# MicroMouse_v03_full_plane.net
KiCad netlist of a schematic drawn in EasyEDA Pro
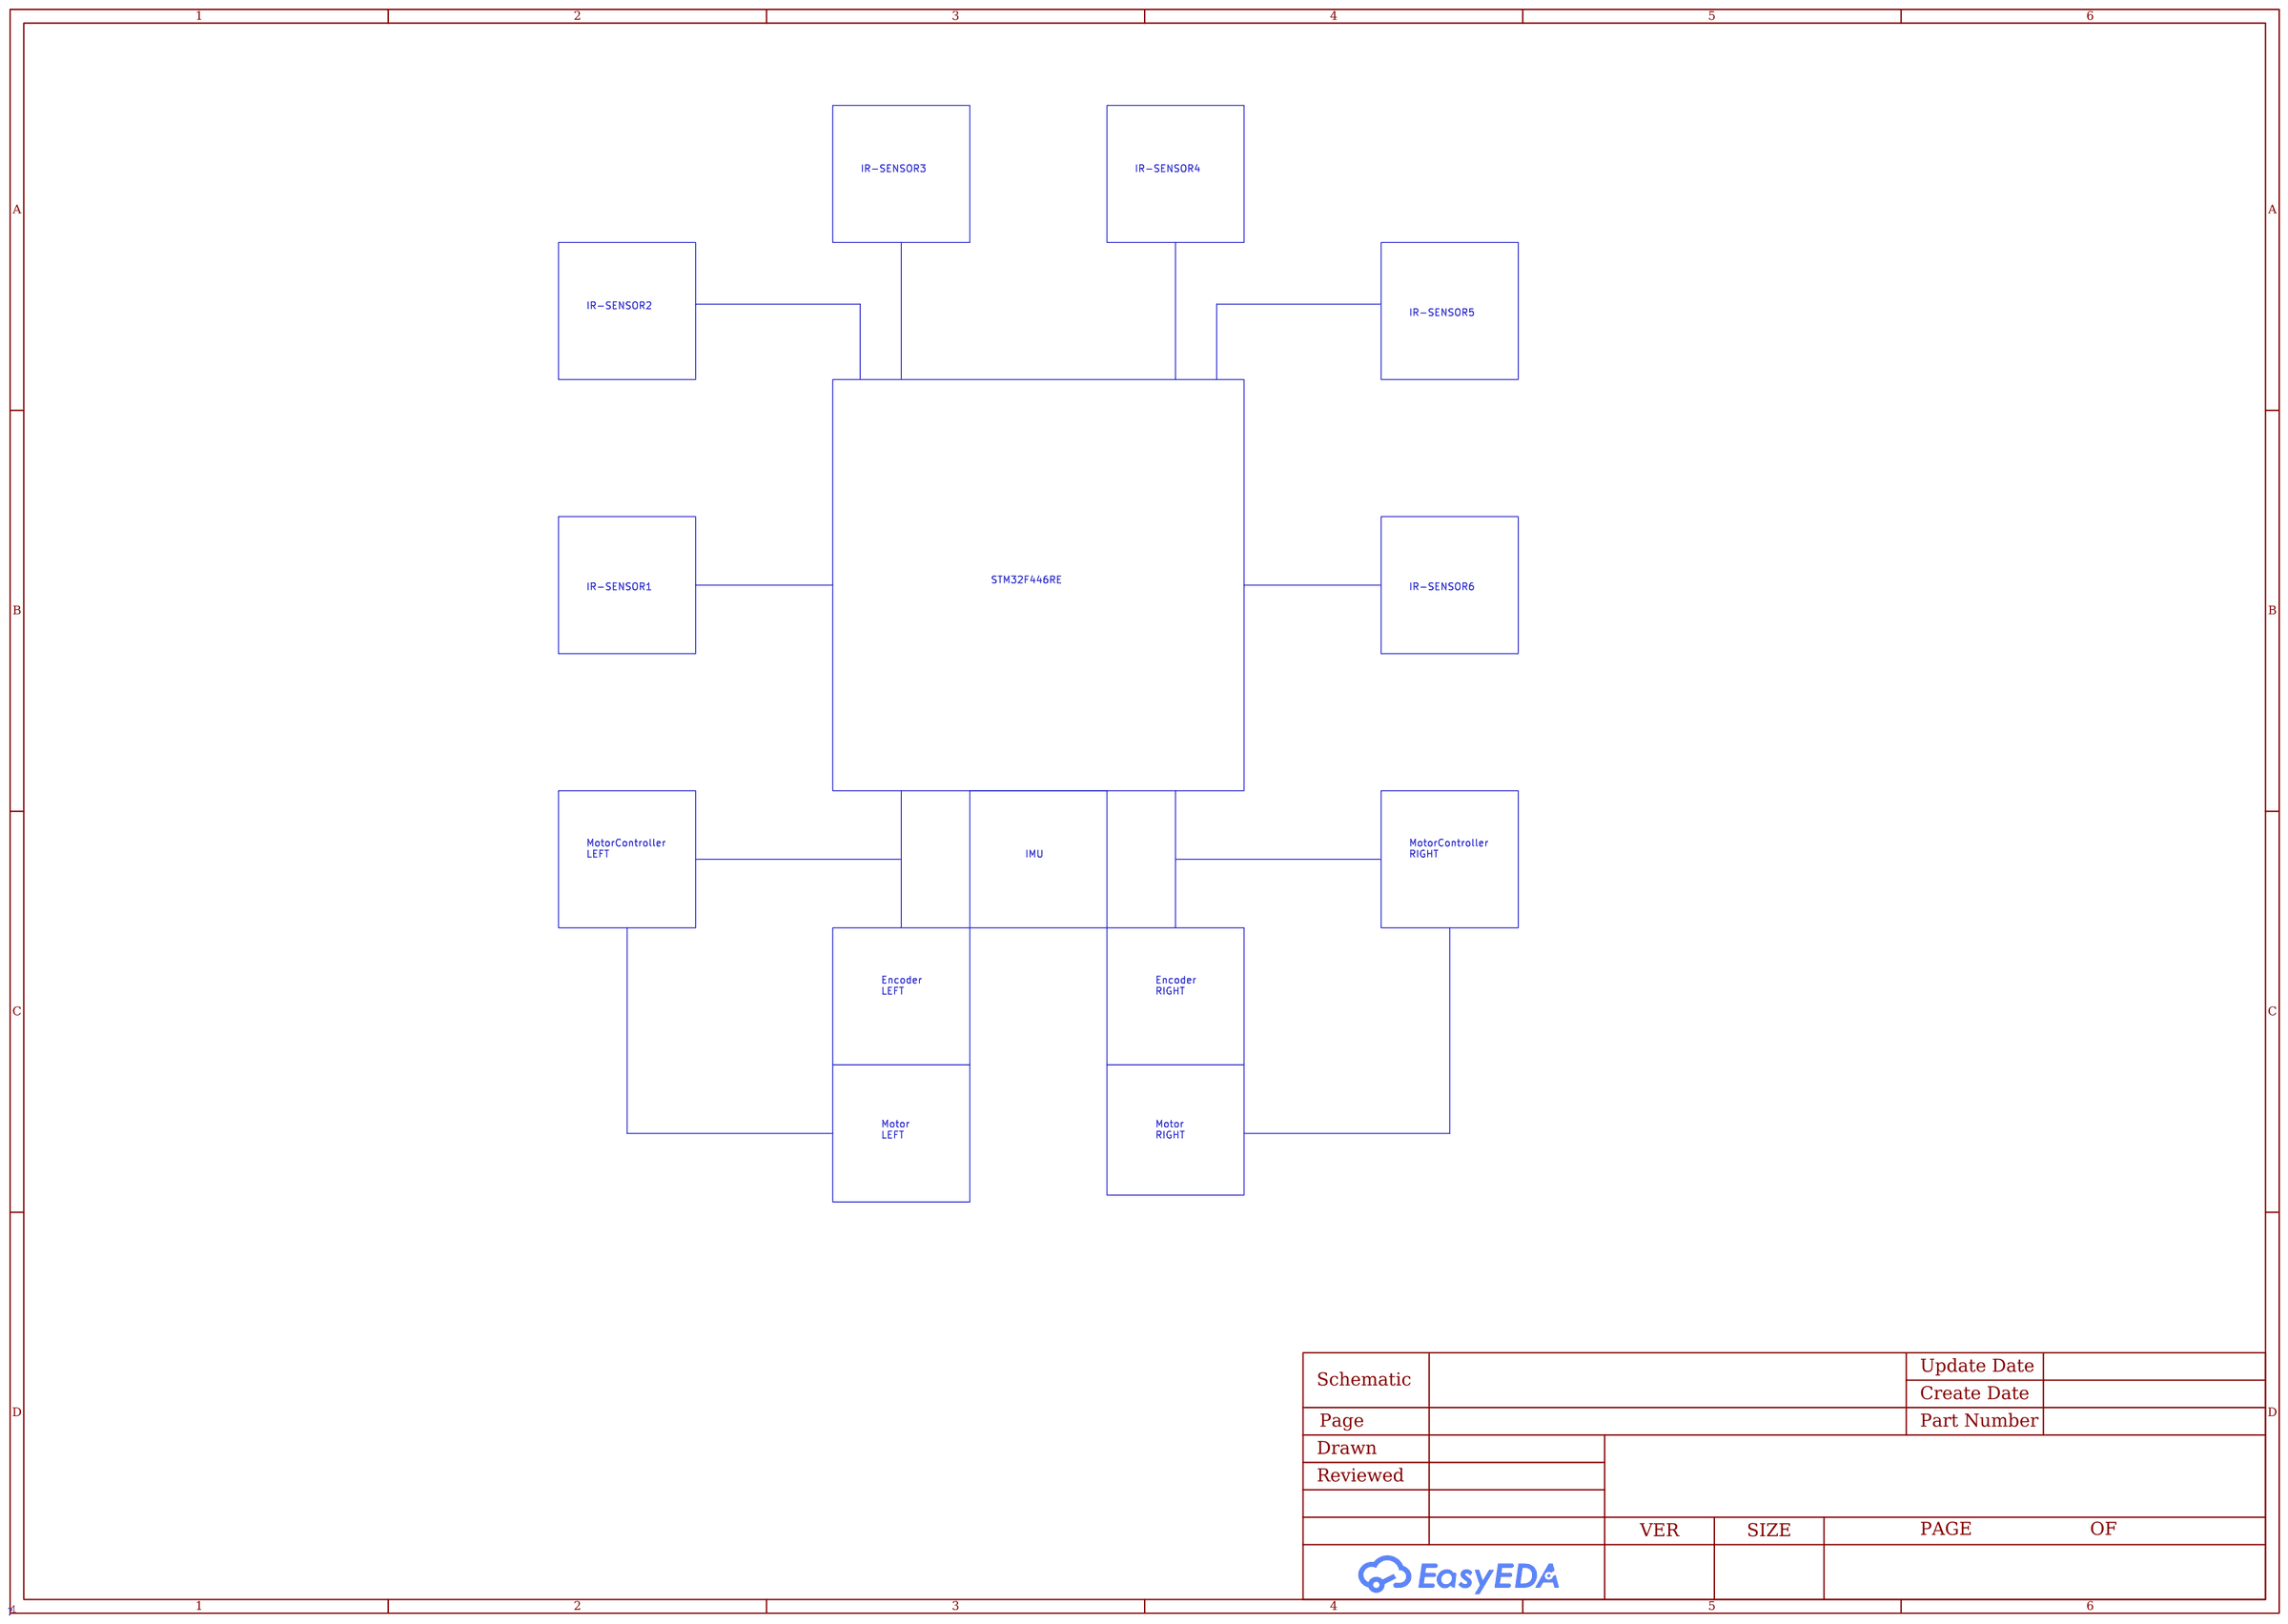
[diagram p0: Overview]
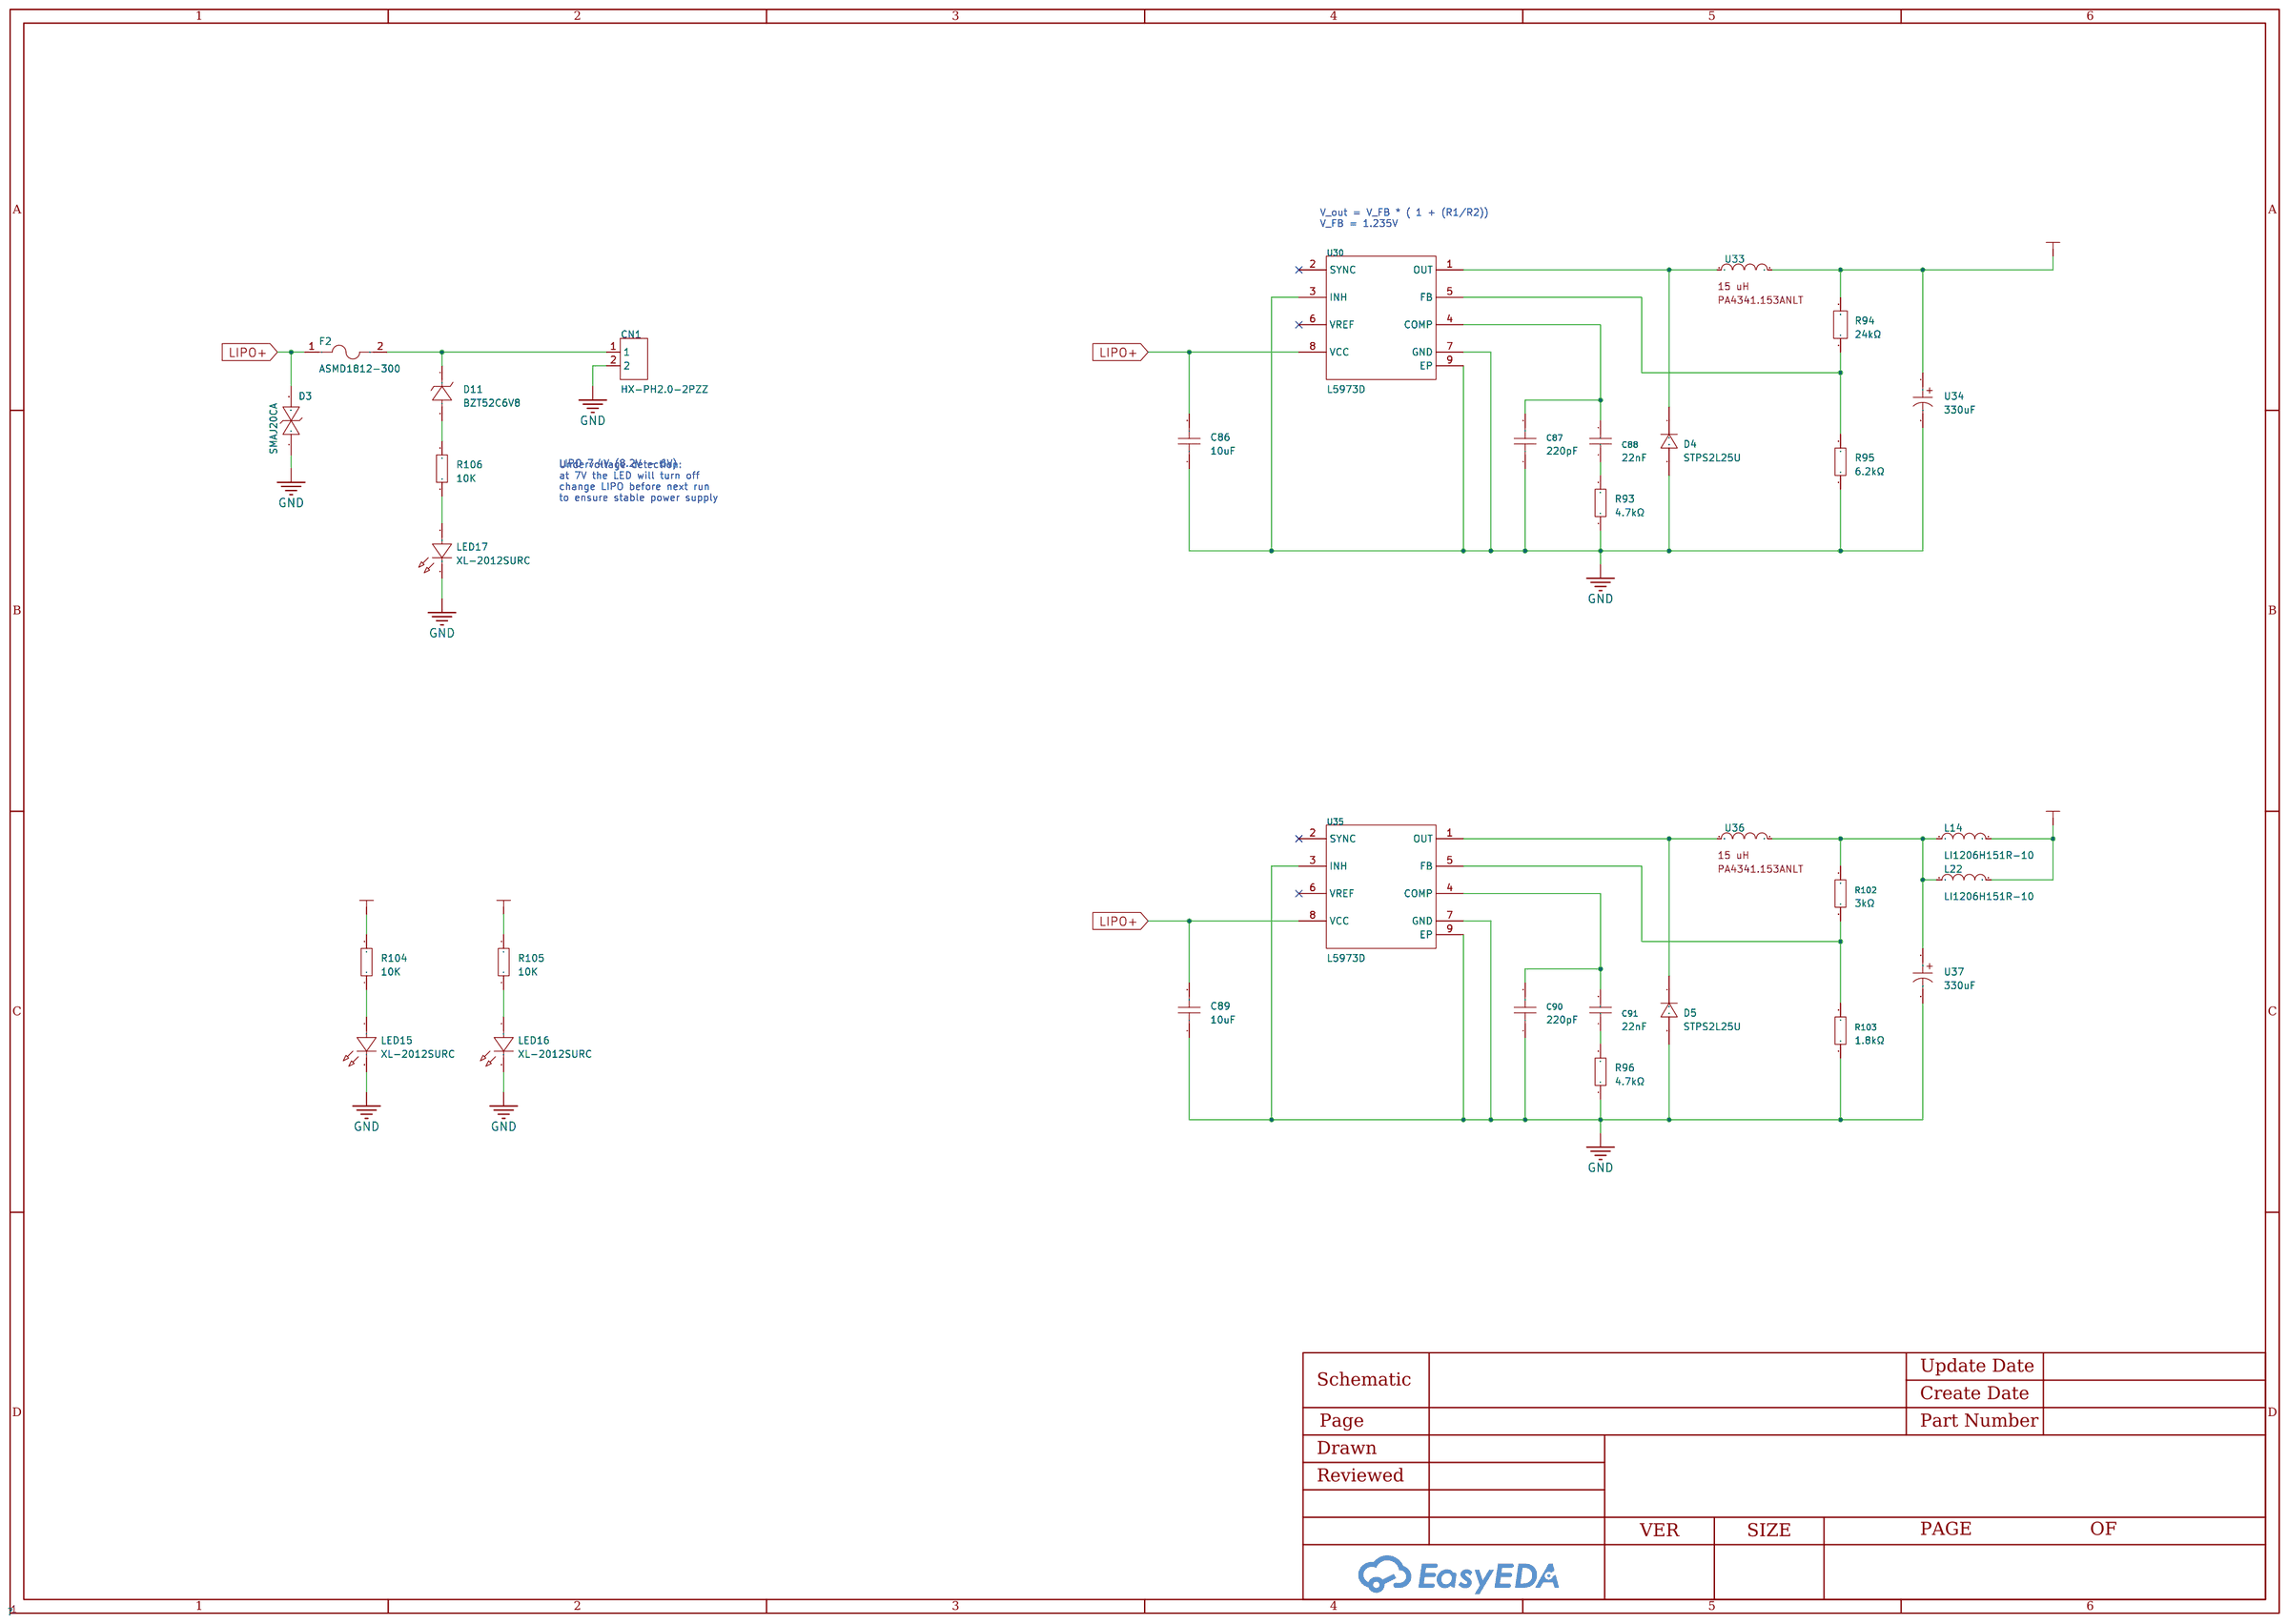
[diagram p1: VCC]
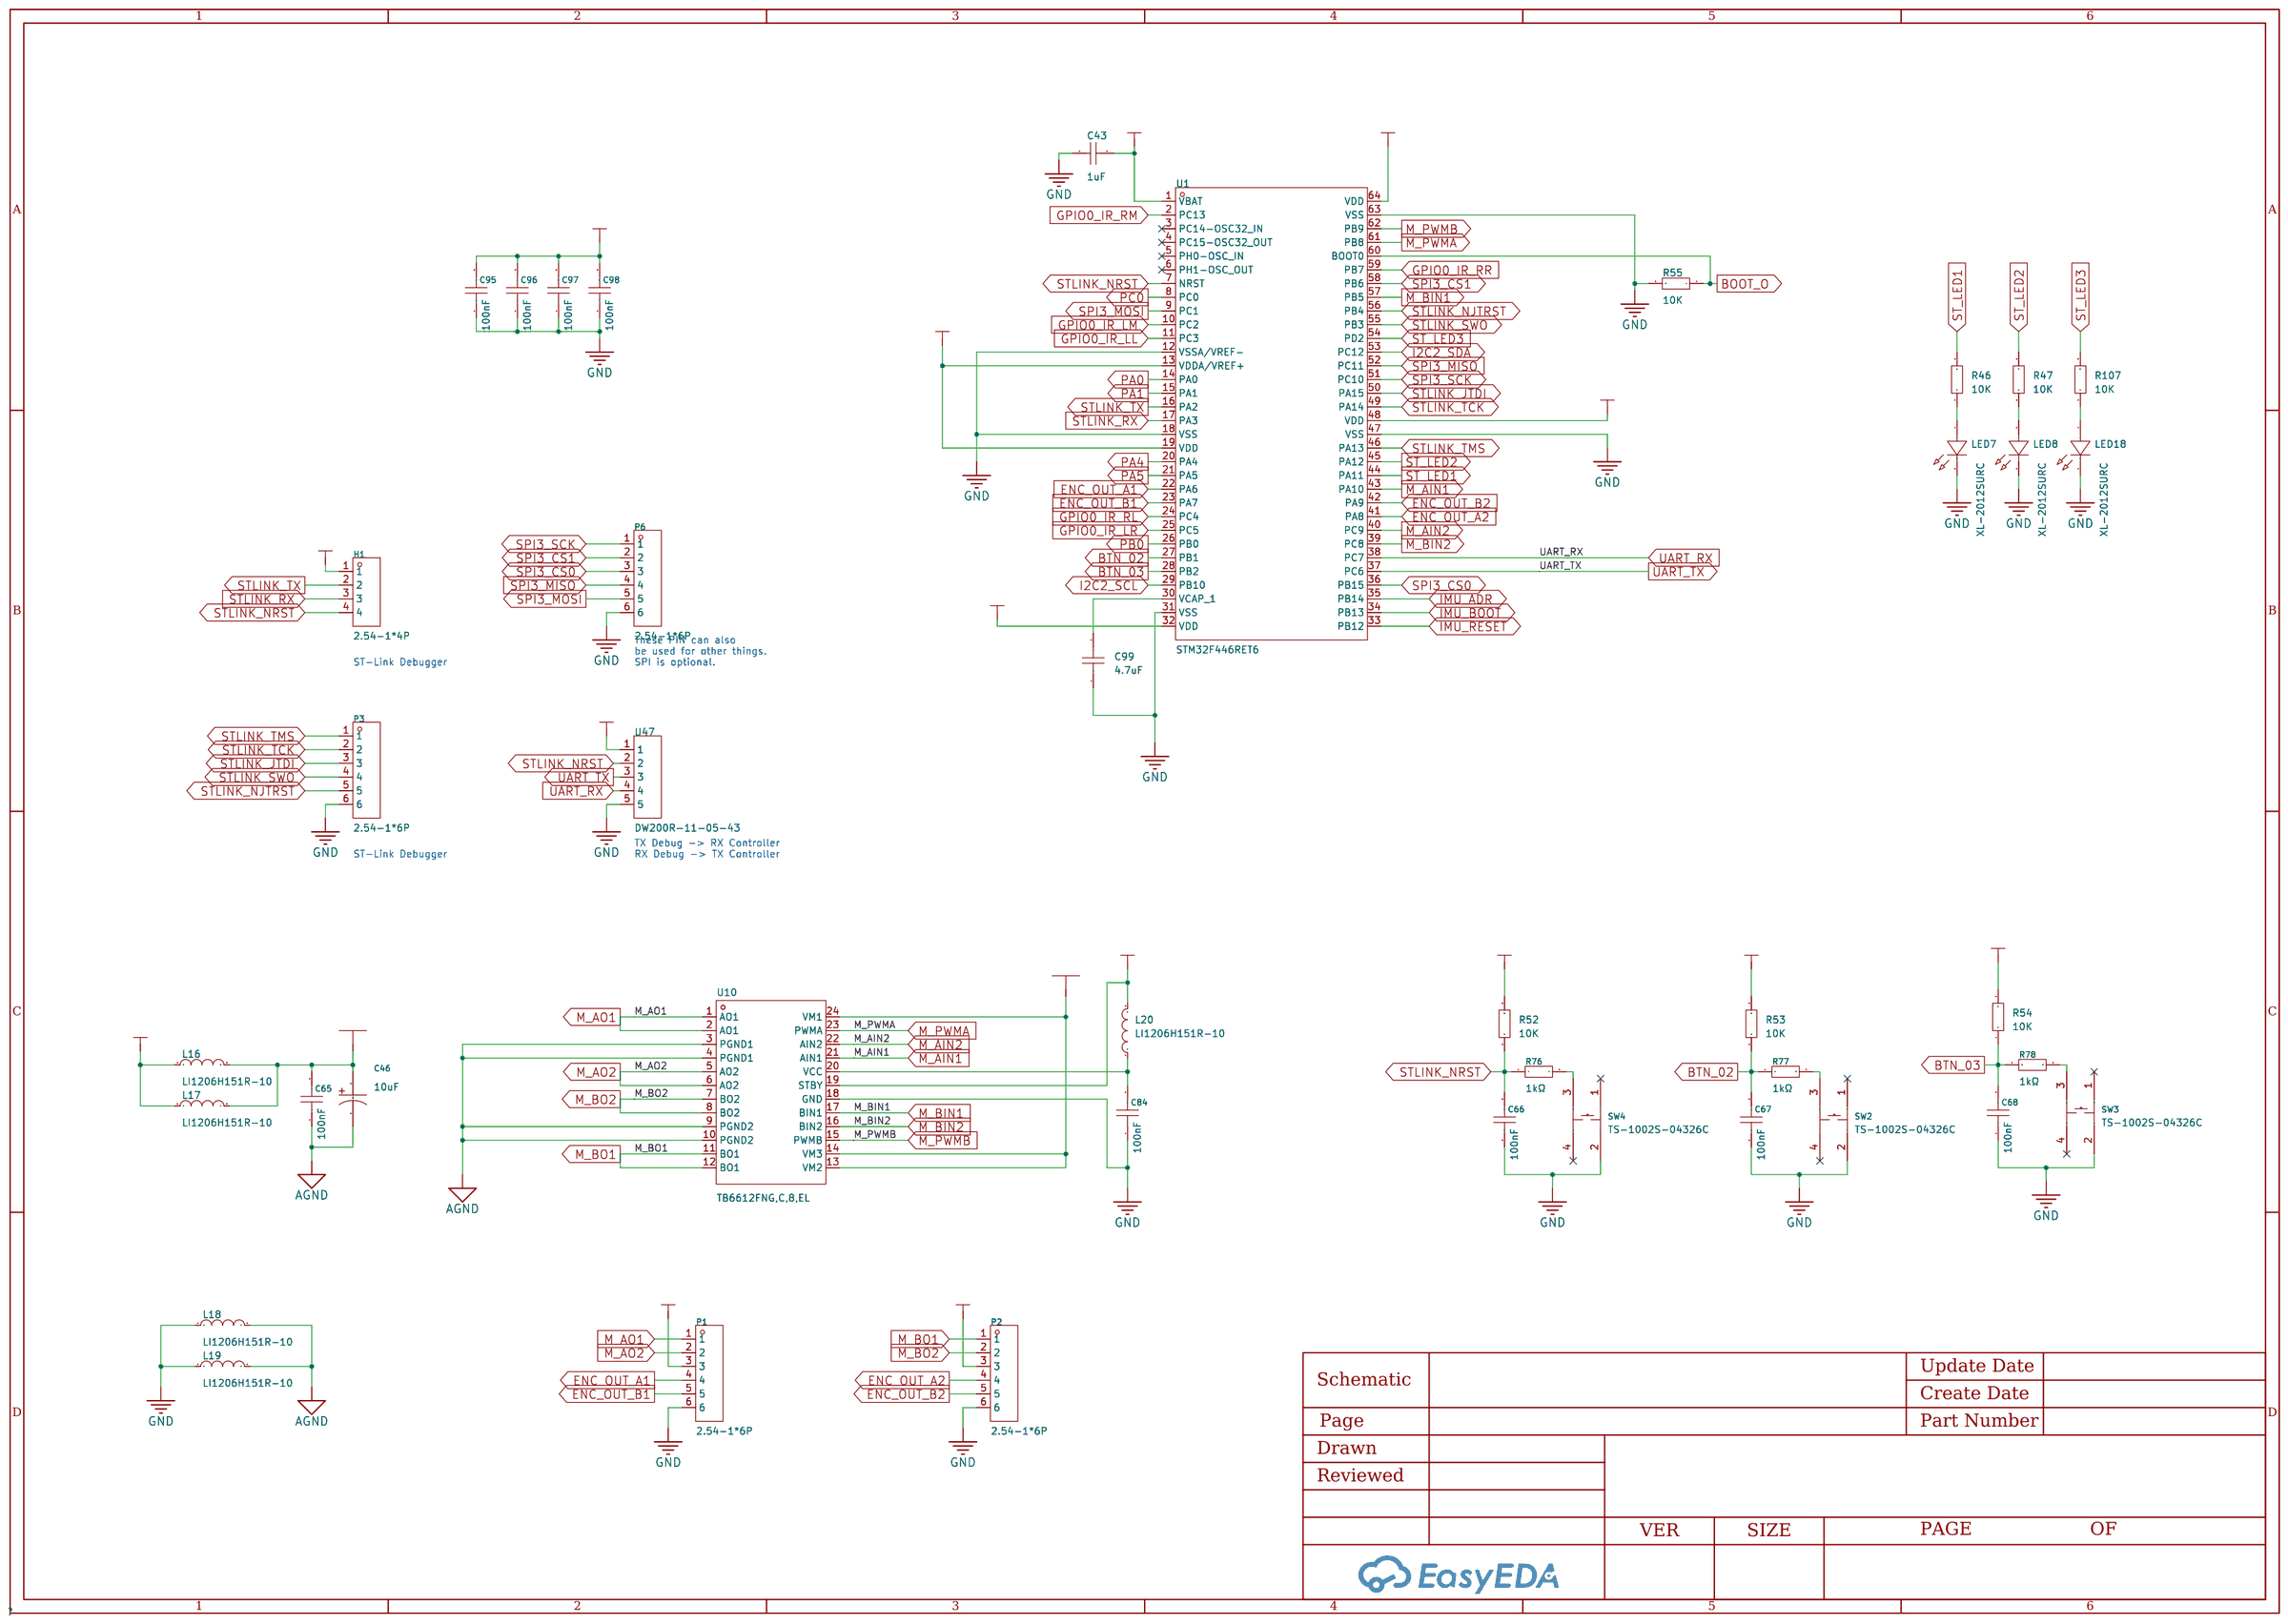
[diagram p2: Controller]
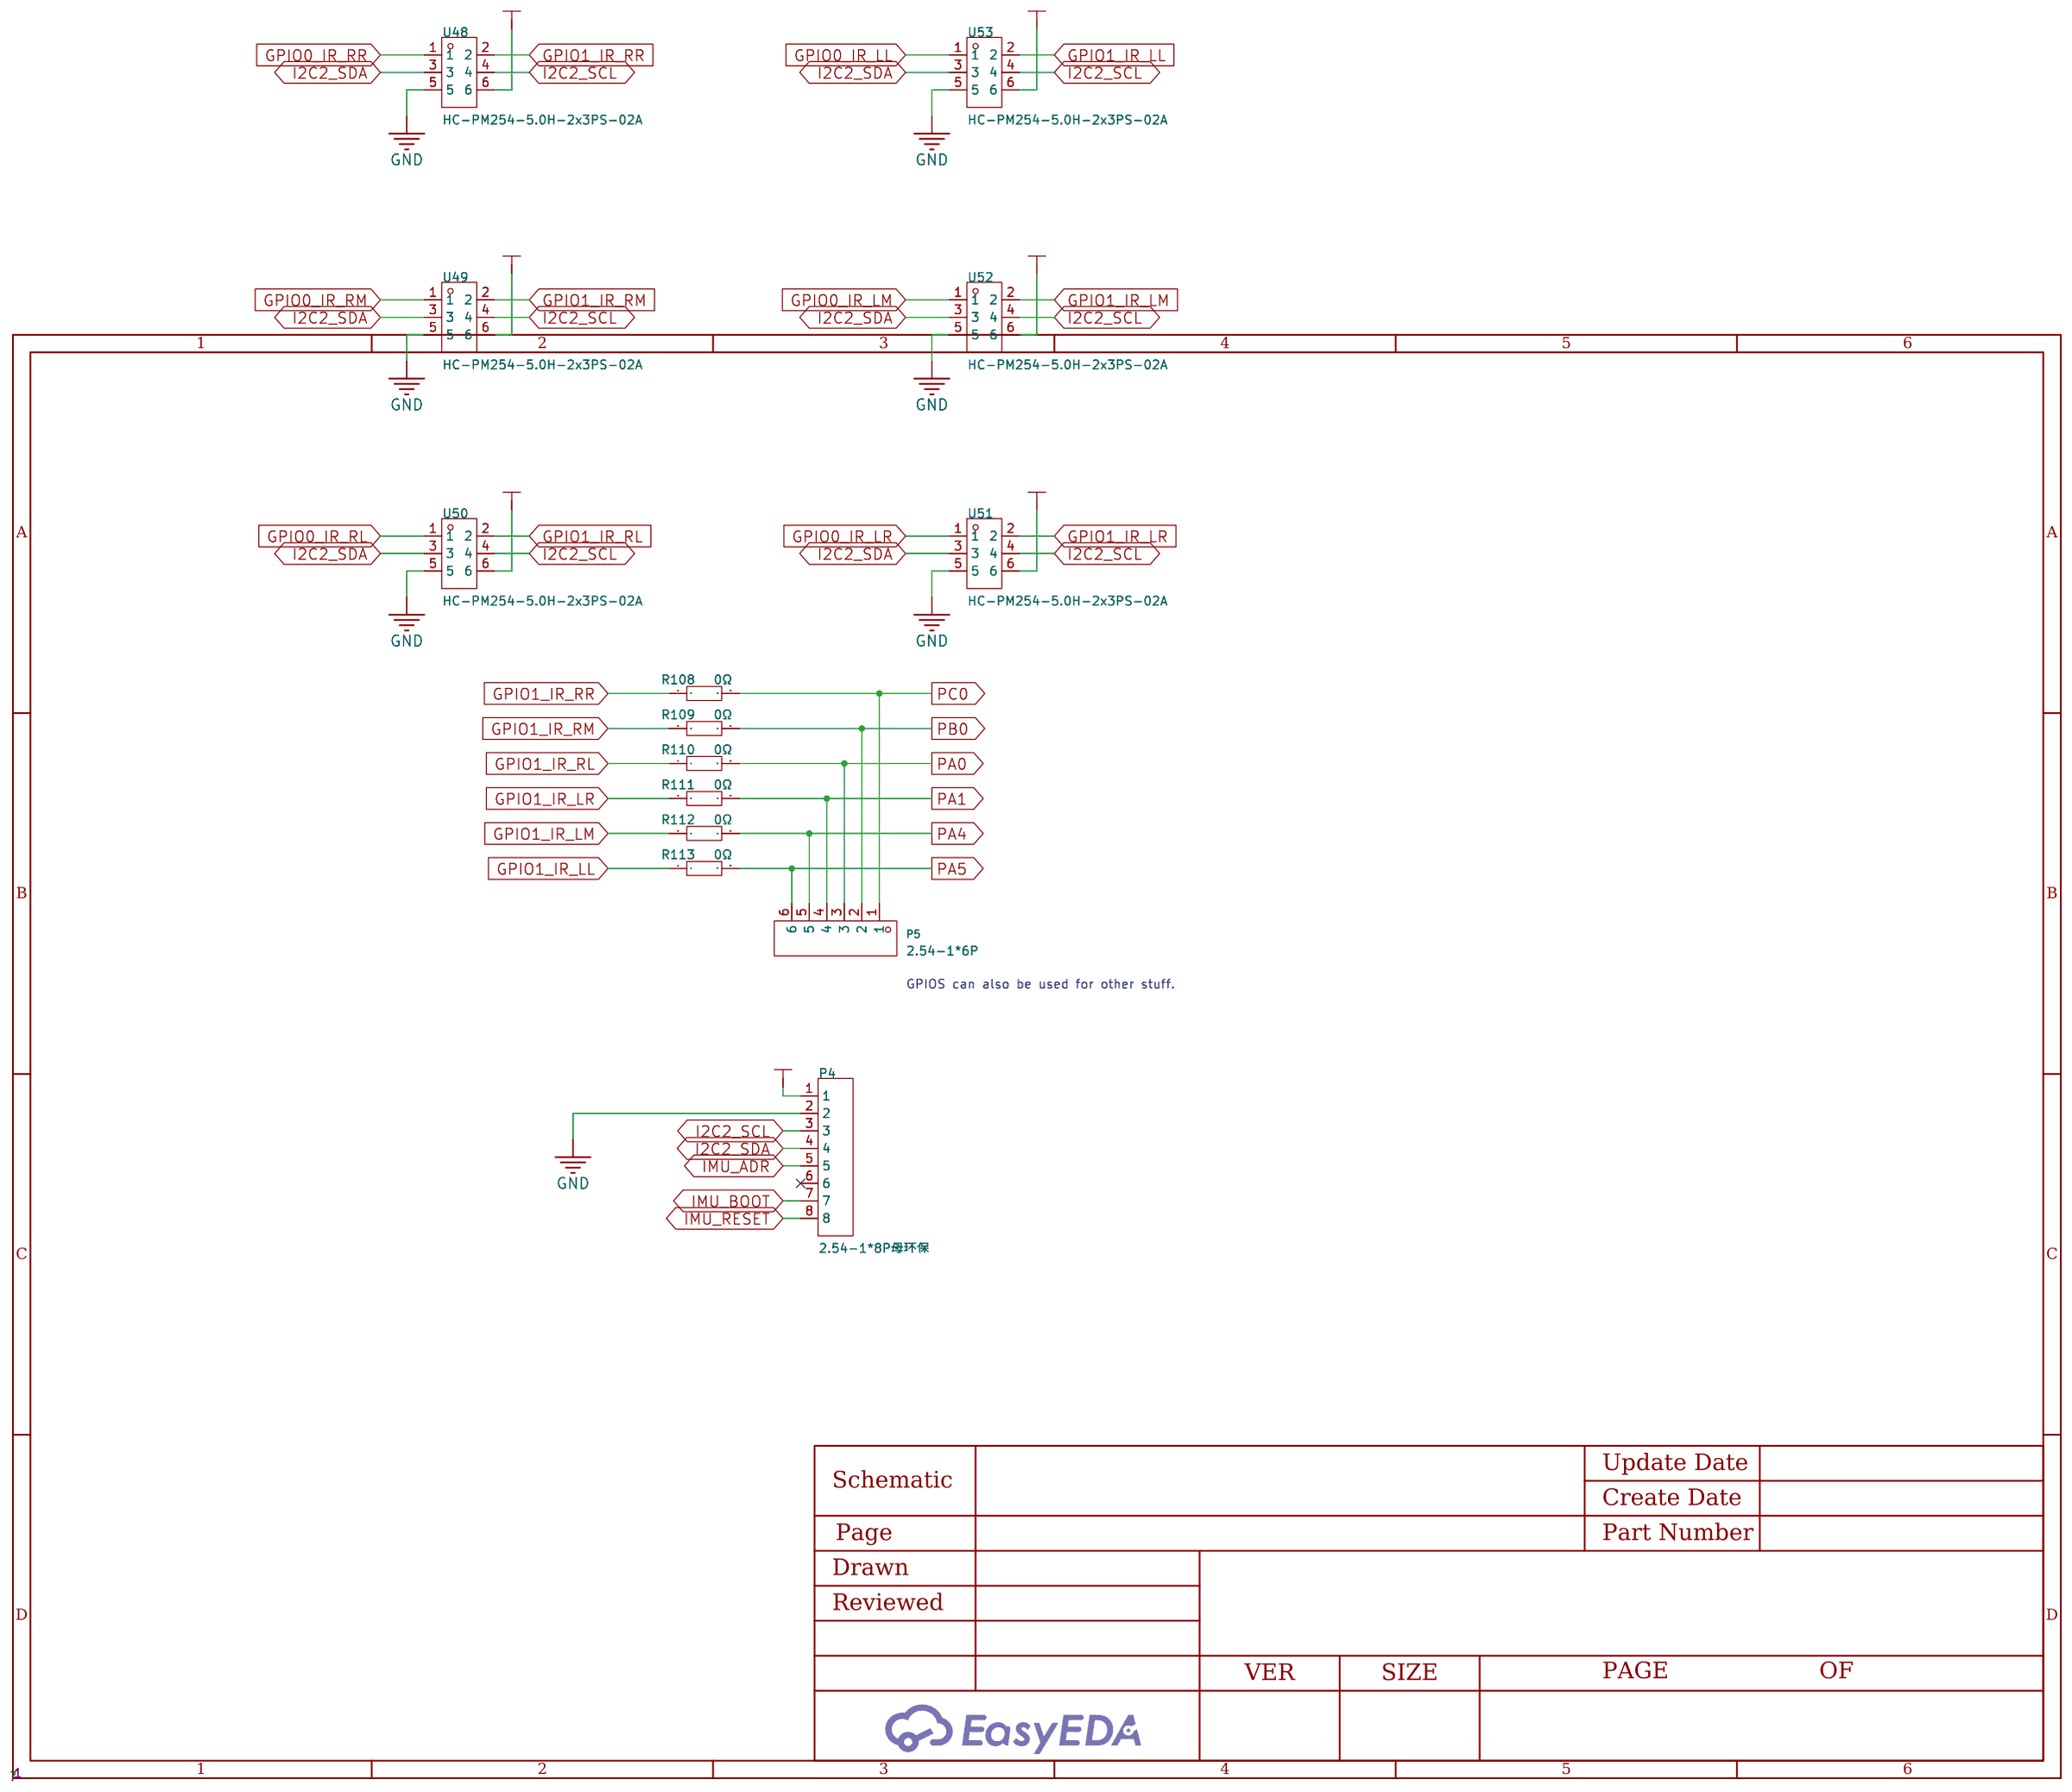
[diagram p3: Sensors]

(export (version "E")
  (design (tool "Eeschema 10.0.6"))
  (components
    (comp (ref "C86")
      (value "10uF")
      (footprint "easyedapro:C0805")
      (description "Capacitance:10uF Tolerance:±10% Tolerance:±10% Voltage Rating:25V Temperature Coefficient:X5R")
      (fields
        (field (name "Manufacturer Part") "CL21A106KAYNNNE")
        (field (name "Manufacturer") "SAMSUNG(三星)")
      )
      (libsource (lib "easyedapro") (part "CL21A106KAYNNNE"))
    )
    (comp (ref "C87")
      (value "220pF")
      (footprint "easyedapro:C0805")
      (description "Capacitance:22nF Tolerance:±10% Tolerance:±10% Voltage Rating:25V Temperature Coefficient:X7R")
      (fields
        (field (name "Manufacturer Part") "CC0805KRX7R8BB223")
        (field (name "Manufacturer") "YAGEO(国巨)")
      )
      (libsource (lib "easyedapro") (part "CC0805KRX7R8BB223"))
    )
    (comp (ref "C88")
      (value "22nF")
      (footprint "easyedapro:C0805")
      (description "Capacitance:220pF Tolerance:±10% Tolerance:±10% Voltage Rating:50V Temperature Coefficient:X7R")
      (fields
        (field (name "Manufacturer Part") "CC0805KRX7R9BB221")
        (field (name "Manufacturer") "YAGEO(国巨)")
      )
      (libsource (lib "easyedapro") (part "CC0805KRX7R9BB221"))
    )
    (comp (ref "C89")
      (value "10uF")
      (footprint "easyedapro:C0805")
      (description "Capacitance:10uF Tolerance:±10% Tolerance:±10% Voltage Rating:25V Temperature Coefficient:X5R")
      (fields
        (field (name "Manufacturer Part") "CL21A106KAYNNNE")
        (field (name "Manufacturer") "SAMSUNG(三星)")
      )
      (libsource (lib "easyedapro") (part "CL21A106KAYNNNE"))
    )
    (comp (ref "C90")
      (value "220pF")
      (footprint "easyedapro:C0805")
      (description "Capacitance:22nF Tolerance:±10% Tolerance:±10% Voltage Rating:25V Temperature Coefficient:X7R")
      (fields
        (field (name "Manufacturer Part") "CC0805KRX7R8BB223")
        (field (name "Manufacturer") "YAGEO(国巨)")
      )
      (libsource (lib "easyedapro") (part "CC0805KRX7R8BB223"))
    )
    (comp (ref "C91")
      (value "22nF")
      (footprint "easyedapro:C0805")
      (description "Capacitance:220pF Tolerance:±10% Tolerance:±10% Voltage Rating:50V Temperature Coefficient:X7R")
      (fields
        (field (name "Manufacturer Part") "CC0805KRX7R9BB221")
        (field (name "Manufacturer") "YAGEO(国巨)")
      )
      (libsource (lib "easyedapro") (part "CC0805KRX7R9BB221"))
    )
    (comp (ref "CN1")
      (value "HX-PH2.0-2PZZ")
      (footprint "easyedapro:CONN-TH_2P-P2.50_HX-PH2.0-2PZZ")
      (fields (field (name "Manufacturer") "hanxia(韩下)"))
      (libsource (lib "easyedapro") (part "HX-PH2.0-2PZZ"))
    )
    (comp (ref "D3")
      (value "SMAJ20CA")
      (footprint "easyedapro:SMA_L4.3-W2.6-LS5.2-BI")
      (fields (field (name "Manufacturer") "High Diode(海德)"))
      (libsource (lib "easyedapro") (part "SMAJ20CA_C514090"))
    )
    (comp (ref "D4")
      (value "STPS2L25U")
      (footprint "easyedapro:SMB_L4.6-W3.6-LS5.3-RD")
      (fields (field (name "Manufacturer") "ST(意法半导体)"))
      (libsource (lib "easyedapro") (part "STPS2L25U"))
    )
    (comp (ref "D5")
      (value "STPS2L25U")
      (footprint "easyedapro:SMB_L4.6-W3.6-LS5.3-RD")
      (fields (field (name "Manufacturer") "ST(意法半导体)"))
      (libsource (lib "easyedapro") (part "STPS2L25U"))
    )
    (comp (ref "D11")
      (value "BZT52C6V8")
      (footprint "easyedapro:SOD-123_L2.7-W1.7-LS3.8-RD")
      (fields (field (name "Manufacturer") "TWGMC(迪嘉)"))
      (libsource (lib "easyedapro") (part "BZT52C6V8_C726998"))
    )
    (comp (ref "F2")
      (value "ASMD1812-300")
      (footprint "easyedapro:F1812")
      (fields (field (name "Manufacturer") "JDTfuse(集电通)"))
      (libsource (lib "easyedapro") (part "ASMD1812-300"))
    )
    (comp (ref "L14")
      (value "LI1206H151R-10")
      (footprint "easyedapro:L1206")
      (description "Impedance @ Frequency:150Ω@100MHz DC Resistance(DCR):150mΩ Number of Circuits:1")
      (fields (field (name "Manufacturer") "Laird(莱尔德)"))
      (libsource (lib "easyedapro") (part "LI1206H151R-10"))
    )
    (comp (ref "L22")
      (value "LI1206H151R-10")
      (footprint "easyedapro:L1206")
      (description "Impedance @ Frequency:150Ω@100MHz DC Resistance(DCR):150mΩ Number of Circuits:1")
      (fields (field (name "Manufacturer") "Laird(莱尔德)"))
      (libsource (lib "easyedapro") (part "LI1206H151R-10"))
    )
    (comp (ref "LED15")
      (value "XL-2012SURC")
      (footprint "easyedapro:LED0805-R-RD")
      (fields (field (name "Manufacturer") "XINGLIGHT(成兴光)"))
      (libsource (lib "easyedapro") (part "XL-2012SURC"))
    )
    (comp (ref "LED16")
      (value "XL-2012SURC")
      (footprint "easyedapro:LED0805-R-RD")
      (fields (field (name "Manufacturer") "XINGLIGHT(成兴光)"))
      (libsource (lib "easyedapro") (part "XL-2012SURC"))
    )
    (comp (ref "LED17")
      (value "XL-2012SURC")
      (footprint "easyedapro:LED0805-R-RD")
      (fields (field (name "Manufacturer") "XINGLIGHT(成兴光)"))
      (libsource (lib "easyedapro") (part "XL-2012SURC"))
    )
    (comp (ref "R93")
      (value "4.7kΩ")
      (footprint "easyedapro:R0603")
      (fields
        (field (name "Manufacturer Part") "0603WAF4701T5E")
        (field (name "Manufacturer") "UNI-ROYAL(厚声)")
      )
      (libsource (lib "easyedapro") (part "0603WAF4701T5E"))
    )
    (comp (ref "R94")
      (value "24kΩ")
      (footprint "easyedapro:R0603")
      (fields (field (name "Manufacturer Part") "FRC0603F2402TS") (field (name "Manufacturer") "FOJAN(富捷)"))
      (libsource (lib "easyedapro") (part "FRC0603F2402TS"))
    )
    (comp (ref "R95")
      (value "6.2kΩ")
      (footprint "easyedapro:R0603")
      (fields
        (field (name "Manufacturer Part") "0603WAF6201T5E")
        (field (name "Manufacturer") "UNI-ROYAL(厚声)")
      )
      (libsource (lib "easyedapro") (part "0603WAF6201T5E"))
    )
    (comp (ref "R96")
      (value "4.7kΩ")
      (footprint "easyedapro:R0603")
      (fields
        (field (name "Manufacturer Part") "0603WAF4701T5E")
        (field (name "Manufacturer") "UNI-ROYAL(厚声)")
      )
      (libsource (lib "easyedapro") (part "0603WAF4701T5E"))
    )
    (comp (ref "R102")
      (value "3kΩ")
      (footprint "easyedapro:R0603")
      (fields
        (field (name "Manufacturer Part") "0603WAF3001T5E")
        (field (name "Manufacturer") "UNI-ROYAL(厚声)")
      )
      (libsource (lib "easyedapro") (part "0603WAF3001T5E"))
    )
    (comp (ref "R103")
      (value "1.8kΩ")
      (footprint "easyedapro:R0603")
      (fields
        (field (name "Manufacturer Part") "0603WAF1801T5E")
        (field (name "Manufacturer") "UNI-ROYAL(厚声)")
      )
      (libsource (lib "easyedapro") (part "0603WAF1801T5E"))
    )
    (comp (ref "R104")
      (value "10K")
      (footprint "easyedapro:R0603")
      (description "DNI")
      (libsource (lib "easyedapro") (part "Res"))
    )
    (comp (ref "R105")
      (value "10K")
      (footprint "easyedapro:R0603")
      (description "DNI")
      (libsource (lib "easyedapro") (part "Res"))
    )
    (comp (ref "R106")
      (value "10K")
      (footprint "easyedapro:R0603")
      (description "DNI")
      (libsource (lib "easyedapro") (part "Res"))
    )
    (comp (ref "U30")
      (value "L5973D")
      (footprint "easyedapro:SOIC-8_L4.9-W3.9-P1.27-LS6.0-BL-EP")
      (fields (field (name "Manufacturer") "ST(意法半导体)"))
      (libsource (lib "easyedapro") (part "L5973D"))
    )
    (comp (ref "U33")
      (value "1.5uH")
      (footprint "easyedapro:IND-SMD_L7.6-W6.9")
      (fields
        (field (name "Manufacturer Part") "PA4341.152NLT")
        (field (name "Manufacturer") "PULSE(普思）")
        (field (name "DC Resistance (DCR)") "PA4341.153ANLT")
        (field (name "Rated Current") "15 uH")
      )
      (libsource (lib "easyedapro") (part "PA4341.152NLT"))
    )
    (comp (ref "U34")
      (value "330uF")
      (footprint "easyedapro:CAP-SMD_BD6.3-L6.6-W6.6-LS7.4-FD")
      (fields (field (name "Manufacturer Part") "RVT1A331M0607") (field (name "Manufacturer") "ROQANG(容强)"))
      (libsource (lib "easyedapro") (part "RVT1A331M0607_C7419412"))
    )
    (comp (ref "U35")
      (value "L5973D")
      (footprint "easyedapro:SOIC-8_L4.9-W3.9-P1.27-LS6.0-BL-EP")
      (fields (field (name "Manufacturer") "ST(意法半导体)"))
      (libsource (lib "easyedapro") (part "L5973D"))
    )
    (comp (ref "U36")
      (value "1.5uH")
      (footprint "easyedapro:IND-SMD_L7.6-W6.9")
      (fields
        (field (name "Manufacturer Part") "PA4341.152NLT")
        (field (name "Manufacturer") "PULSE(普思）")
        (field (name "DC Resistance (DCR)") "PA4341.153ANLT")
        (field (name "Rated Current") "15 uH")
      )
      (libsource (lib "easyedapro") (part "PA4341.152NLT"))
    )
    (comp (ref "U37")
      (value "330uF")
      (footprint "easyedapro:CAP-SMD_BD6.3-L6.6-W6.6-LS7.4-FD")
      (fields (field (name "Manufacturer Part") "RVT1A331M0607") (field (name "Manufacturer") "ROQANG(容强)"))
      (libsource (lib "easyedapro") (part "RVT1A331M0607_C7419412"))
    )
    (comp (ref "C43")
      (value "1uF")
      (footprint "easyedapro:C0603")
      (fields
        (field (name "Manufacturer Part") "CL10A105KO8NNNC")
        (field (name "Manufacturer") "SAMSUNG(三星)")
      )
      (libsource (lib "easyedapro") (part "CL10A105KO8NNNC"))
    )
    (comp (ref "C46")
      (value "10uF")
      (footprint "easyedapro:CAP-TH_BD5.0-P5.00-D1.0-FD")
      (fields
        (field (name "Manufacturer Part") "UVZ1C100MDD1TA")
        (field (name "Manufacturer") "Nichicon(尼吉康)")
      )
      (libsource (lib "easyedapro") (part "UVZ1C100MDD1TA"))
    )
    (comp (ref "C65")
      (value "100nF")
      (footprint "easyedapro:C0603")
      (fields
        (field (name "Manufacturer Part") "CC0603KRX7R6BB104")
        (field (name "Manufacturer") "YAGEO(国巨)")
      )
      (libsource (lib "easyedapro") (part "CC0603KRX7R6BB104"))
    )
    (comp (ref "C66")
      (value "100nF")
      (footprint "easyedapro:C0603")
      (fields
        (field (name "Manufacturer Part") "CC0603KRX7R6BB104")
        (field (name "Manufacturer") "YAGEO(国巨)")
      )
      (libsource (lib "easyedapro") (part "CC0603KRX7R6BB104"))
    )
    (comp (ref "C67")
      (value "100nF")
      (footprint "easyedapro:C0603")
      (fields
        (field (name "Manufacturer Part") "CC0603KRX7R6BB104")
        (field (name "Manufacturer") "YAGEO(国巨)")
      )
      (libsource (lib "easyedapro") (part "CC0603KRX7R6BB104"))
    )
    (comp (ref "C68")
      (value "100nF")
      (footprint "easyedapro:C0603")
      (fields
        (field (name "Manufacturer Part") "CC0603KRX7R6BB104")
        (field (name "Manufacturer") "YAGEO(国巨)")
      )
      (libsource (lib "easyedapro") (part "CC0603KRX7R6BB104"))
    )
    (comp (ref "C84")
      (value "100nF")
      (footprint "easyedapro:C0603")
      (fields
        (field (name "Manufacturer Part") "CC0603KRX7R6BB104")
        (field (name "Manufacturer") "YAGEO(国巨)")
      )
      (libsource (lib "easyedapro") (part "CC0603KRX7R6BB104"))
    )
    (comp (ref "C95")
      (value "100nF")
      (footprint "easyedapro:C0603")
      (fields
        (field (name "Manufacturer Part") "CC0603KRX7R6BB104")
        (field (name "Manufacturer") "YAGEO(国巨)")
      )
      (libsource (lib "easyedapro") (part "CC0603KRX7R6BB104"))
    )
    (comp (ref "C96")
      (value "100nF")
      (footprint "easyedapro:C0603")
      (fields
        (field (name "Manufacturer Part") "CC0603KRX7R6BB104")
        (field (name "Manufacturer") "YAGEO(国巨)")
      )
      (libsource (lib "easyedapro") (part "CC0603KRX7R6BB104"))
    )
    (comp (ref "C97")
      (value "100nF")
      (footprint "easyedapro:C0603")
      (fields
        (field (name "Manufacturer Part") "CC0603KRX7R6BB104")
        (field (name "Manufacturer") "YAGEO(国巨)")
      )
      (libsource (lib "easyedapro") (part "CC0603KRX7R6BB104"))
    )
    (comp (ref "C98")
      (value "100nF")
      (footprint "easyedapro:C0603")
      (fields
        (field (name "Manufacturer Part") "CC0603KRX7R6BB104")
        (field (name "Manufacturer") "YAGEO(国巨)")
      )
      (libsource (lib "easyedapro") (part "CC0603KRX7R6BB104"))
    )
    (comp (ref "C99")
      (value "4.7uF")
      (footprint "easyedapro:C0603")
      (description "Capacitance:4.7uF Tolerance:±10% Tolerance:±10% Voltage Rating:25V Temperature Coefficient:X5R")
      (fields
        (field (name "Manufacturer Part") "CGA0603X5R475K250JT")
        (field (name "Manufacturer") "HRE(芯声)")
      )
      (libsource (lib "easyedapro") (part "CGA0603X5R475K250JT"))
    )
    (comp (ref "H1")
      (value "2.54-1*4P")
      (footprint "easyedapro:HDR-TH_4P-P2.54-V-F")
      (fields (field (name "Manufacturer") "BOOMELE(博穆精密)"))
      (libsource (lib "easyedapro") (part "2.54-1*4P母"))
    )
    (comp (ref "L16")
      (value "LI1206H151R-10")
      (footprint "easyedapro:L1206")
      (description "Impedance @ Frequency:150Ω@100MHz DC Resistance(DCR):150mΩ Number of Circuits:1")
      (fields (field (name "Manufacturer") "Laird(莱尔德)"))
      (libsource (lib "easyedapro") (part "LI1206H151R-10"))
    )
    (comp (ref "L17")
      (value "LI1206H151R-10")
      (footprint "easyedapro:L1206")
      (description "Impedance @ Frequency:150Ω@100MHz DC Resistance(DCR):150mΩ Number of Circuits:1")
      (fields (field (name "Manufacturer") "Laird(莱尔德)"))
      (libsource (lib "easyedapro") (part "LI1206H151R-10"))
    )
    (comp (ref "L18")
      (value "LI1206H151R-10")
      (footprint "easyedapro:L1206")
      (description "Impedance @ Frequency:150Ω@100MHz DC Resistance(DCR):150mΩ Number of Circuits:1")
      (fields (field (name "Manufacturer") "Laird(莱尔德)"))
      (libsource (lib "easyedapro") (part "LI1206H151R-10"))
    )
    (comp (ref "L19")
      (value "LI1206H151R-10")
      (footprint "easyedapro:L1206")
      (description "Impedance @ Frequency:150Ω@100MHz DC Resistance(DCR):150mΩ Number of Circuits:1")
      (fields (field (name "Manufacturer") "Laird(莱尔德)"))
      (libsource (lib "easyedapro") (part "LI1206H151R-10"))
    )
    (comp (ref "L20")
      (value "LI1206H151R-10")
      (footprint "easyedapro:L1206")
      (description "Impedance @ Frequency:150Ω@100MHz DC Resistance(DCR):150mΩ Number of Circuits:1")
      (fields (field (name "Manufacturer") "Laird(莱尔德)"))
      (libsource (lib "easyedapro") (part "LI1206H151R-10"))
    )
    (comp (ref "LED7")
      (value "XL-2012SURC")
      (footprint "easyedapro:LED0805-R-RD")
      (fields (field (name "Manufacturer") "XINGLIGHT(成兴光)"))
      (libsource (lib "easyedapro") (part "XL-2012SURC"))
    )
    (comp (ref "LED8")
      (value "XL-2012SURC")
      (footprint "easyedapro:LED0805-R-RD")
      (fields (field (name "Manufacturer") "XINGLIGHT(成兴光)"))
      (libsource (lib "easyedapro") (part "XL-2012SURC"))
    )
    (comp (ref "LED18")
      (value "XL-2012SURC")
      (footprint "easyedapro:LED0805-R-RD")
      (fields (field (name "Manufacturer") "XINGLIGHT(成兴光)"))
      (libsource (lib "easyedapro") (part "XL-2012SURC"))
    )
    (comp (ref "P1")
      (value "2.54-1*6P")
      (footprint "easyedapro:HDR-TH_6P-P2.54-V-F")
      (fields (field (name "Manufacturer") "BOOMELE(博穆精密)"))
      (libsource (lib "easyedapro") (part "Header-Female-2.54_1x6"))
    )
    (comp (ref "P2")
      (value "2.54-1*6P")
      (footprint "easyedapro:HDR-TH_6P-P2.54-V-F")
      (fields (field (name "Manufacturer") "BOOMELE(博穆精密)"))
      (libsource (lib "easyedapro") (part "Header-Female-2.54_1x6"))
    )
    (comp (ref "P3")
      (value "2.54-1*6P")
      (footprint "easyedapro:HDR-TH_6P-P2.54-V-F")
      (fields (field (name "Manufacturer") "BOOMELE(博穆精密)"))
      (libsource (lib "easyedapro") (part "Header-Female-2.54_1x6"))
    )
    (comp (ref "P6")
      (value "2.54-1*6P")
      (footprint "easyedapro:HDR-TH_6P-P2.54-V-F")
      (fields (field (name "Manufacturer") "BOOMELE(博穆精密)"))
      (libsource (lib "easyedapro") (part "Header-Female-2.54_1x6"))
    )
    (comp (ref "R46")
      (value "10K")
      (footprint "easyedapro:R0603")
      (description "DNI")
      (libsource (lib "easyedapro") (part "Res"))
    )
    (comp (ref "R47")
      (value "10K")
      (footprint "easyedapro:R0603")
      (description "DNI")
      (libsource (lib "easyedapro") (part "Res"))
    )
    (comp (ref "R52")
      (value "10K")
      (footprint "easyedapro:R0603")
      (description "DNI")
      (libsource (lib "easyedapro") (part "Res"))
    )
    (comp (ref "R53")
      (value "10K")
      (footprint "easyedapro:R0603")
      (description "DNI")
      (libsource (lib "easyedapro") (part "Res"))
    )
    (comp (ref "R54")
      (value "10K")
      (footprint "easyedapro:R0603")
      (description "DNI")
      (libsource (lib "easyedapro") (part "Res"))
    )
    (comp (ref "R55")
      (value "10K")
      (footprint "easyedapro:R0603")
      (description "DNI")
      (libsource (lib "easyedapro") (part "Res"))
    )
    (comp (ref "R76")
      (value "1kΩ")
      (footprint "easyedapro:R0603")
      (fields
        (field (name "Manufacturer Part") "0603WAF1001T5E")
        (field (name "Manufacturer") "UNI-ROYAL(厚声)")
      )
      (libsource (lib "easyedapro") (part "0603WAF1001T5E"))
    )
    (comp (ref "R77")
      (value "1kΩ")
      (footprint "easyedapro:R0603")
      (fields
        (field (name "Manufacturer Part") "0603WAF1001T5E")
        (field (name "Manufacturer") "UNI-ROYAL(厚声)")
      )
      (libsource (lib "easyedapro") (part "0603WAF1001T5E"))
    )
    (comp (ref "R78")
      (value "1kΩ")
      (footprint "easyedapro:R0603")
      (fields
        (field (name "Manufacturer Part") "0603WAF1001T5E")
        (field (name "Manufacturer") "UNI-ROYAL(厚声)")
      )
      (libsource (lib "easyedapro") (part "0603WAF1001T5E"))
    )
    (comp (ref "R107")
      (value "10K")
      (footprint "easyedapro:R0603")
      (description "DNI")
      (libsource (lib "easyedapro") (part "Res"))
    )
    (comp (ref "SW2")
      (value "TS-1002S-04326C")
      (footprint "easyedapro:KEY-SMD_4P-L6.0-W6.0-P4.50-LS9.0")
      (fields (field (name "Manufacturer") "XUNPU(讯普)"))
      (libsource (lib "easyedapro") (part "TS-1002S-04326C"))
    )
    (comp (ref "SW3")
      (value "TS-1002S-04326C")
      (footprint "easyedapro:KEY-SMD_4P-L6.0-W6.0-P4.50-LS9.0")
      (fields (field (name "Manufacturer") "XUNPU(讯普)"))
      (libsource (lib "easyedapro") (part "TS-1002S-04326C"))
    )
    (comp (ref "SW4")
      (value "TS-1002S-04326C")
      (footprint "easyedapro:KEY-SMD_4P-L6.0-W6.0-P4.50-LS9.0")
      (fields (field (name "Manufacturer") "XUNPU(讯普)"))
      (libsource (lib "easyedapro") (part "TS-1002S-04326C"))
    )
    (comp (ref "U1")
      (value "STM32F446RET6")
      (footprint "easyedapro:LQFP-64_L10.0-W10.0-P0.50-LS12.0-BL")
      (fields (field (name "Manufacturer") "ST(意法半导体)"))
      (libsource (lib "easyedapro") (part "STM32F446RET6"))
    )
    (comp (ref "U10")
      (value "TB6612FNG,C,8,EL")
      (footprint "easyedapro:SSOP-24_L8.3-W5.6-P0.65-LS7.6-BL")
      (fields (field (name "Manufacturer") "TOSHIBA(东芝)"))
      (libsource (lib "easyedapro") (part "TB6612FNG,C,8,EL"))
    )
    (comp (ref "U47")
      (value "DW200R-11-05-43")
      (footprint "easyedapro:HDR-TH_5P-P2.00-V-F")
      (fields (field (name "Manufacturer") "DEALON(德艺隆)"))
      (libsource (lib "easyedapro") (part "DW200R-11-05-43"))
    )
    (comp (ref "P4")
      (value "2.54-1*8P母环保")
      (footprint "easyedapro:HDR-TH_8P-P2.54-V-F_2")
      (fields (field (name "Manufacturer") "BOOMELE(博穆精密)"))
      (libsource (lib "easyedapro") (part "Header-Female-2.54_1x8"))
    )
    (comp (ref "P5")
      (value "2.54-1*6P")
      (footprint "easyedapro:HDR-TH_6P-P2.54-V-F")
      (fields (field (name "Manufacturer") "BOOMELE(博穆精密)"))
      (libsource (lib "easyedapro") (part "Header-Female-2.54_1x6"))
    )
    (comp (ref "R108")
      (value "0Ω")
      (footprint "easyedapro:R0603")
      (fields
        (field (name "Manufacturer Part") "0603WAF0000T5E")
        (field (name "Manufacturer") "UNI-ROYAL(厚声)")
      )
      (libsource (lib "easyedapro") (part "0603WAF0000T5E"))
    )
    (comp (ref "R109")
      (value "0Ω")
      (footprint "easyedapro:R0603")
      (fields
        (field (name "Manufacturer Part") "0603WAF0000T5E")
        (field (name "Manufacturer") "UNI-ROYAL(厚声)")
      )
      (libsource (lib "easyedapro") (part "0603WAF0000T5E"))
    )
    (comp (ref "R110")
      (value "0Ω")
      (footprint "easyedapro:R0603")
      (fields
        (field (name "Manufacturer Part") "0603WAF0000T5E")
        (field (name "Manufacturer") "UNI-ROYAL(厚声)")
      )
      (libsource (lib "easyedapro") (part "0603WAF0000T5E"))
    )
    (comp (ref "R111")
      (value "0Ω")
      (footprint "easyedapro:R0603")
      (fields
        (field (name "Manufacturer Part") "0603WAF0000T5E")
        (field (name "Manufacturer") "UNI-ROYAL(厚声)")
      )
      (libsource (lib "easyedapro") (part "0603WAF0000T5E"))
    )
    (comp (ref "R112")
      (value "0Ω")
      (footprint "easyedapro:R0603")
      (fields
        (field (name "Manufacturer Part") "0603WAF0000T5E")
        (field (name "Manufacturer") "UNI-ROYAL(厚声)")
      )
      (libsource (lib "easyedapro") (part "0603WAF0000T5E"))
    )
    (comp (ref "R113")
      (value "0Ω")
      (footprint "easyedapro:R0603")
      (fields
        (field (name "Manufacturer Part") "0603WAF0000T5E")
        (field (name "Manufacturer") "UNI-ROYAL(厚声)")
      )
      (libsource (lib "easyedapro") (part "0603WAF0000T5E"))
    )
    (comp (ref "U48")
      (value "HC-PM254-5.0H-2x3PS-02A")
      (footprint "easyedapro:CONN-SMD_HC-PM254-5.0H-2X3PS-02A")
      (fields (field (name "Manufacturer") "HC(虹成电子)"))
      (libsource (lib "easyedapro") (part "HC-PM254-5.0H-2X3PS-02A"))
    )
    (comp (ref "U49")
      (value "HC-PM254-5.0H-2x3PS-02A")
      (footprint "easyedapro:CONN-SMD_HC-PM254-5.0H-2X3PS-02A")
      (fields (field (name "Manufacturer") "HC(虹成电子)"))
      (libsource (lib "easyedapro") (part "HC-PM254-5.0H-2X3PS-02A"))
    )
    (comp (ref "U50")
      (value "HC-PM254-5.0H-2x3PS-02A")
      (footprint "easyedapro:CONN-SMD_HC-PM254-5.0H-2X3PS-02A")
      (fields (field (name "Manufacturer") "HC(虹成电子)"))
      (libsource (lib "easyedapro") (part "HC-PM254-5.0H-2X3PS-02A"))
    )
    (comp (ref "U51")
      (value "HC-PM254-5.0H-2x3PS-02A")
      (footprint "easyedapro:CONN-SMD_HC-PM254-5.0H-2X3PS-02A")
      (fields (field (name "Manufacturer") "HC(虹成电子)"))
      (libsource (lib "easyedapro") (part "HC-PM254-5.0H-2X3PS-02A"))
    )
    (comp (ref "U52")
      (value "HC-PM254-5.0H-2x3PS-02A")
      (footprint "easyedapro:CONN-SMD_HC-PM254-5.0H-2X3PS-02A")
      (fields (field (name "Manufacturer") "HC(虹成电子)"))
      (libsource (lib "easyedapro") (part "HC-PM254-5.0H-2X3PS-02A"))
    )
    (comp (ref "U53")
      (value "HC-PM254-5.0H-2x3PS-02A")
      (footprint "easyedapro:CONN-SMD_HC-PM254-5.0H-2X3PS-02A")
      (fields (field (name "Manufacturer") "HC(虹成电子)"))
      (libsource (lib "easyedapro") (part "HC-PM254-5.0H-2X3PS-02A"))
    )
  )
  (nets
    (net (code "1") (name "+3V3") (class "Default")
      (node (ref "C43") (pin "1") (pinfunction "1_1") (pintype "input"))
      (node (ref "C95") (pin "2") (pinfunction "2_2") (pintype "input"))
      (node (ref "C96") (pin "2") (pinfunction "2_2") (pintype "input"))
      (node (ref "C97") (pin "2") (pinfunction "2_2") (pintype "input"))
      (node (ref "C98") (pin "2") (pinfunction "2_2") (pintype "input"))
      (node (ref "H1") (pin "1") (pinfunction "1_1") (pintype "input"))
      (node (ref "L14") (pin "2") (pinfunction "2_2") (pintype "unspecified"))
      (node (ref "L20") (pin "2") (pinfunction "2_2") (pintype "unspecified"))
      (node (ref "L22") (pin "2") (pinfunction "2_2") (pintype "unspecified"))
      (node (ref "P1") (pin "3") (pinfunction "3_3") (pintype "input"))
      (node (ref "P2") (pin "3") (pinfunction "3_3") (pintype "input"))
      (node (ref "P4") (pin "1") (pinfunction "1_1") (pintype "unspecified"))
      (node (ref "R105") (pin "2") (pinfunction "2_2") (pintype "input"))
      (node (ref "R52") (pin "2") (pinfunction "2_2") (pintype "input"))
      (node (ref "R53") (pin "2") (pinfunction "2_2") (pintype "input"))
      (node (ref "R54") (pin "2") (pinfunction "2_2") (pintype "input"))
      (node (ref "U1") (pin "1") (pinfunction "VBAT_1") (pintype "unspecified"))
      (node (ref "U1") (pin "13") (pinfunction "VDDA/VREF+_13") (pintype "unspecified"))
      (node (ref "U1") (pin "19") (pinfunction "VDD_19") (pintype "unspecified"))
      (node (ref "U1") (pin "32") (pinfunction "VDD_32") (pintype "unspecified"))
      (node (ref "U1") (pin "48") (pinfunction "VDD_48") (pintype "unspecified"))
      (node (ref "U1") (pin "64") (pinfunction "VDD_64") (pintype "unspecified"))
      (node (ref "U10") (pin "19") (pinfunction "STBY_19") (pintype "unspecified"))
      (node (ref "U47") (pin "1") (pinfunction "1_1") (pintype "unspecified"))
      (node (ref "U48") (pin "6") (pinfunction "6_6") (pintype "unspecified"))
      (node (ref "U49") (pin "6") (pinfunction "6_6") (pintype "unspecified"))
      (node (ref "U50") (pin "6") (pinfunction "6_6") (pintype "unspecified"))
      (node (ref "U51") (pin "6") (pinfunction "6_6") (pintype "unspecified"))
      (node (ref "U52") (pin "6") (pinfunction "6_6") (pintype "unspecified"))
      (node (ref "U53") (pin "6") (pinfunction "6_6") (pintype "unspecified"))
    )
    (net (code "2") (name "+6V_MOT") (class "Default")
      (node (ref "C46") (pin "1") (pinfunction "1_1") (pintype "input"))
      (node (ref "C65") (pin "2") (pinfunction "2_2") (pintype "input"))
      (node (ref "L16") (pin "2") (pinfunction "2_2") (pintype "unspecified"))
      (node (ref "L17") (pin "2") (pinfunction "2_2") (pintype "unspecified"))
      (node (ref "U10") (pin "13") (pinfunction "VM2_13") (pintype "unspecified"))
      (node (ref "U10") (pin "14") (pinfunction "VM3_14") (pintype "unspecified"))
      (node (ref "U10") (pin "24") (pinfunction "VM1_24") (pintype "unspecified"))
    )
    (net (code "3") (name "6V") (class "Default")
      (node (ref "L16") (pin "1") (pinfunction "1_1") (pintype "unspecified"))
      (node (ref "L17") (pin "1") (pinfunction "1_1") (pintype "unspecified"))
      (node (ref "R104") (pin "2") (pinfunction "2_2") (pintype "input"))
      (node (ref "R94") (pin "2") (pinfunction "2_2") (pintype "unspecified"))
      (node (ref "U33") (pin "2") (pinfunction "2_2") (pintype "unspecified"))
      (node (ref "U34") (pin "1") (pinfunction "1_1") (pintype "input"))
    )
    (net (code "4") (name "AGND") (class "Default")
      (node (ref "C46") (pin "2") (pinfunction "2_2") (pintype "input"))
      (node (ref "C65") (pin "1") (pinfunction "1_1") (pintype "input"))
      (node (ref "L18") (pin "2") (pinfunction "2_2") (pintype "unspecified"))
      (node (ref "L19") (pin "2") (pinfunction "2_2") (pintype "unspecified"))
      (node (ref "U10") (pin "10") (pinfunction "PGND2_10") (pintype "unspecified"))
      (node (ref "U10") (pin "3") (pinfunction "PGND1_3") (pintype "unspecified"))
      (node (ref "U10") (pin "4") (pinfunction "PGND1_4") (pintype "unspecified"))
      (node (ref "U10") (pin "9") (pinfunction "PGND2_9") (pintype "unspecified"))
    )
    (net (code "5") (name "BOOT_O") (class "Default")
      (node (ref "R55") (pin "1") (pinfunction "1_1") (pintype "input"))
      (node (ref "U1") (pin "60") (pinfunction "BOOT0_60") (pintype "unspecified"))
    )
    (net (code "6") (name "BTN_02") (class "Default")
      (node (ref "C67") (pin "2") (pinfunction "2_2") (pintype "input"))
      (node (ref "R53") (pin "1") (pinfunction "1_1") (pintype "input"))
      (node (ref "R77") (pin "1") (pinfunction "1_1") (pintype "input"))
      (node (ref "U1") (pin "27") (pinfunction "PB1_27") (pintype "unspecified"))
    )
    (net (code "7") (name "BTN_03") (class "Default")
      (node (ref "C68") (pin "2") (pinfunction "2_2") (pintype "input"))
      (node (ref "R54") (pin "1") (pinfunction "1_1") (pintype "input"))
      (node (ref "R78") (pin "1") (pinfunction "1_1") (pintype "input"))
      (node (ref "U1") (pin "28") (pinfunction "PB2_28") (pintype "unspecified"))
    )
    (net (code "8") (name "ENC_OUT_A1") (class "Default")
      (node (ref "P1") (pin "4") (pinfunction "4_4") (pintype "input"))
      (node (ref "U1") (pin "22") (pinfunction "PA6_22") (pintype "unspecified"))
    )
    (net (code "9") (name "ENC_OUT_A2") (class "Default")
      (node (ref "P2") (pin "4") (pinfunction "4_4") (pintype "input"))
      (node (ref "U1") (pin "41") (pinfunction "PA8_41") (pintype "unspecified"))
    )
    (net (code "10") (name "ENC_OUT_B1") (class "Default")
      (node (ref "P1") (pin "5") (pinfunction "5_5") (pintype "input"))
      (node (ref "U1") (pin "23") (pinfunction "PA7_23") (pintype "unspecified"))
    )
    (net (code "11") (name "ENC_OUT_B2") (class "Default")
      (node (ref "P2") (pin "5") (pinfunction "5_5") (pintype "input"))
      (node (ref "U1") (pin "42") (pinfunction "PA9_42") (pintype "unspecified"))
    )
    (net (code "12") (name "GND") (class "Default")
      (node (ref "C43") (pin "2") (pinfunction "2_2") (pintype "input"))
      (node (ref "C66") (pin "1") (pinfunction "1_1") (pintype "input"))
      (node (ref "C67") (pin "1") (pinfunction "1_1") (pintype "input"))
      (node (ref "C68") (pin "1") (pinfunction "1_1") (pintype "input"))
      (node (ref "C84") (pin "1") (pinfunction "1_1") (pintype "input"))
      (node (ref "C86") (pin "1") (pinfunction "1_1") (pintype "unspecified"))
      (node (ref "C87") (pin "1") (pinfunction "1_1") (pintype "input"))
      (node (ref "C89") (pin "1") (pinfunction "1_1") (pintype "unspecified"))
      (node (ref "C90") (pin "1") (pinfunction "1_1") (pintype "input"))
      (node (ref "C95") (pin "1") (pinfunction "1_1") (pintype "input"))
      (node (ref "C96") (pin "1") (pinfunction "1_1") (pintype "input"))
      (node (ref "C97") (pin "1") (pinfunction "1_1") (pintype "input"))
      (node (ref "C98") (pin "1") (pinfunction "1_1") (pintype "input"))
      (node (ref "C99") (pin "1") (pinfunction "1_1") (pintype "unspecified"))
      (node (ref "CN1") (pin "2") (pinfunction "2_2") (pintype "unspecified"))
      (node (ref "D3") (pin "1") (pinfunction "1_1") (pintype "input"))
      (node (ref "D4") (pin "2") (pinfunction "2_2") (pintype "unspecified"))
      (node (ref "D5") (pin "2") (pinfunction "2_2") (pintype "unspecified"))
      (node (ref "L18") (pin "1") (pinfunction "1_1") (pintype "unspecified"))
      (node (ref "L19") (pin "1") (pinfunction "1_1") (pintype "unspecified"))
      (node (ref "LED15") (pin "2") (pinfunction "K_2") (pintype "unspecified"))
      (node (ref "LED16") (pin "2") (pinfunction "K_2") (pintype "unspecified"))
      (node (ref "LED17") (pin "2") (pinfunction "K_2") (pintype "unspecified"))
      (node (ref "LED18") (pin "2") (pinfunction "K_2") (pintype "unspecified"))
      (node (ref "LED7") (pin "2") (pinfunction "K_2") (pintype "unspecified"))
      (node (ref "LED8") (pin "2") (pinfunction "K_2") (pintype "unspecified"))
      (node (ref "P1") (pin "6") (pinfunction "6_6") (pintype "input"))
      (node (ref "P2") (pin "6") (pinfunction "6_6") (pintype "input"))
      (node (ref "P3") (pin "6") (pinfunction "6_6") (pintype "input"))
      (node (ref "P4") (pin "2") (pinfunction "2_2") (pintype "unspecified"))
      (node (ref "P6") (pin "6") (pinfunction "6_6") (pintype "input"))
      (node (ref "R103") (pin "1") (pinfunction "1_1") (pintype "input"))
      (node (ref "R55") (pin "2") (pinfunction "2_2") (pintype "input"))
      (node (ref "R93") (pin "1") (pinfunction "1_1") (pintype "input"))
      (node (ref "R95") (pin "1") (pinfunction "1_1") (pintype "input"))
      (node (ref "R96") (pin "1") (pinfunction "1_1") (pintype "input"))
      (node (ref "SW2") (pin "2") (pinfunction "2_2") (pintype "input"))
      (node (ref "SW3") (pin "2") (pinfunction "2_2") (pintype "input"))
      (node (ref "SW4") (pin "2") (pinfunction "2_2") (pintype "input"))
      (node (ref "U1") (pin "12") (pinfunction "VSSA/VREF-_12") (pintype "unspecified"))
      (node (ref "U1") (pin "18") (pinfunction "VSS_18") (pintype "unspecified"))
      (node (ref "U1") (pin "31") (pinfunction "VSS_31") (pintype "unspecified"))
      (node (ref "U1") (pin "47") (pinfunction "VSS_47") (pintype "unspecified"))
      (node (ref "U1") (pin "63") (pinfunction "VSS_63") (pintype "unspecified"))
      (node (ref "U10") (pin "18") (pinfunction "GND_18") (pintype "unspecified"))
      (node (ref "U30") (pin "3") (pinfunction "INH_3") (pintype "input"))
      (node (ref "U30") (pin "7") (pinfunction "GND_7") (pintype "input"))
      (node (ref "U30") (pin "9") (pinfunction "EP_9") (pintype "input"))
      (node (ref "U34") (pin "2") (pinfunction "2_2") (pintype "input"))
      (node (ref "U35") (pin "3") (pinfunction "INH_3") (pintype "input"))
      (node (ref "U35") (pin "7") (pinfunction "GND_7") (pintype "input"))
      (node (ref "U35") (pin "9") (pinfunction "EP_9") (pintype "input"))
      (node (ref "U37") (pin "2") (pinfunction "2_2") (pintype "input"))
      (node (ref "U47") (pin "5") (pinfunction "5_5") (pintype "unspecified"))
      (node (ref "U48") (pin "5") (pinfunction "5_5") (pintype "unspecified"))
      (node (ref "U49") (pin "5") (pinfunction "5_5") (pintype "unspecified"))
      (node (ref "U50") (pin "5") (pinfunction "5_5") (pintype "unspecified"))
      (node (ref "U51") (pin "5") (pinfunction "5_5") (pintype "unspecified"))
      (node (ref "U52") (pin "5") (pinfunction "5_5") (pintype "unspecified"))
      (node (ref "U53") (pin "5") (pinfunction "5_5") (pintype "unspecified"))
    )
    (net (code "13") (name "GPIO0_IR_LL") (class "Default")
      (node (ref "U1") (pin "11") (pinfunction "PC3_11") (pintype "unspecified"))
      (node (ref "U53") (pin "1") (pinfunction "1_1") (pintype "unspecified"))
    )
    (net (code "14") (name "GPIO0_IR_LM") (class "Default")
      (node (ref "U1") (pin "10") (pinfunction "PC2_10") (pintype "unspecified"))
      (node (ref "U52") (pin "1") (pinfunction "1_1") (pintype "unspecified"))
    )
    (net (code "15") (name "GPIO0_IR_LR") (class "Default")
      (node (ref "U1") (pin "25") (pinfunction "PC5_25") (pintype "unspecified"))
      (node (ref "U51") (pin "1") (pinfunction "1_1") (pintype "unspecified"))
    )
    (net (code "16") (name "GPIO0_IR_RL") (class "Default")
      (node (ref "U1") (pin "24") (pinfunction "PC4_24") (pintype "unspecified"))
      (node (ref "U50") (pin "1") (pinfunction "1_1") (pintype "unspecified"))
    )
    (net (code "17") (name "GPIO0_IR_RM") (class "Default")
      (node (ref "U1") (pin "2") (pinfunction "PC13_2") (pintype "unspecified"))
      (node (ref "U49") (pin "1") (pinfunction "1_1") (pintype "unspecified"))
    )
    (net (code "18") (name "GPIO0_IR_RR") (class "Default")
      (node (ref "U1") (pin "59") (pinfunction "PB7_59") (pintype "unspecified"))
      (node (ref "U48") (pin "1") (pinfunction "1_1") (pintype "unspecified"))
    )
    (net (code "19") (name "GPIO1_IR_LL") (class "Default")
      (node (ref "R113") (pin "1") (pinfunction "1_1") (pintype "input"))
      (node (ref "U53") (pin "2") (pinfunction "2_2") (pintype "unspecified"))
    )
    (net (code "20") (name "GPIO1_IR_LM") (class "Default")
      (node (ref "R112") (pin "1") (pinfunction "1_1") (pintype "input"))
      (node (ref "U52") (pin "2") (pinfunction "2_2") (pintype "unspecified"))
    )
    (net (code "21") (name "GPIO1_IR_LR") (class "Default")
      (node (ref "R111") (pin "1") (pinfunction "1_1") (pintype "input"))
      (node (ref "U51") (pin "2") (pinfunction "2_2") (pintype "unspecified"))
    )
    (net (code "22") (name "GPIO1_IR_RL") (class "Default")
      (node (ref "R110") (pin "1") (pinfunction "1_1") (pintype "input"))
      (node (ref "U50") (pin "2") (pinfunction "2_2") (pintype "unspecified"))
    )
    (net (code "23") (name "GPIO1_IR_RM") (class "Default")
      (node (ref "R109") (pin "1") (pinfunction "1_1") (pintype "input"))
      (node (ref "U49") (pin "2") (pinfunction "2_2") (pintype "unspecified"))
    )
    (net (code "24") (name "GPIO1_IR_RR") (class "Default")
      (node (ref "R108") (pin "1") (pinfunction "1_1") (pintype "input"))
      (node (ref "U48") (pin "2") (pinfunction "2_2") (pintype "unspecified"))
    )
    (net (code "25") (name "I2C2_SCL") (class "Default")
      (node (ref "P4") (pin "3") (pinfunction "3_3") (pintype "unspecified"))
      (node (ref "U1") (pin "29") (pinfunction "PB10_29") (pintype "unspecified"))
      (node (ref "U48") (pin "4") (pinfunction "4_4") (pintype "unspecified"))
      (node (ref "U49") (pin "4") (pinfunction "4_4") (pintype "unspecified"))
      (node (ref "U50") (pin "4") (pinfunction "4_4") (pintype "unspecified"))
      (node (ref "U51") (pin "4") (pinfunction "4_4") (pintype "unspecified"))
      (node (ref "U52") (pin "4") (pinfunction "4_4") (pintype "unspecified"))
      (node (ref "U53") (pin "4") (pinfunction "4_4") (pintype "unspecified"))
    )
    (net (code "26") (name "I2C2_SDA") (class "Default")
      (node (ref "P4") (pin "4") (pinfunction "4_4") (pintype "unspecified"))
      (node (ref "U1") (pin "53") (pinfunction "PC12_53") (pintype "unspecified"))
      (node (ref "U48") (pin "3") (pinfunction "3_3") (pintype "unspecified"))
      (node (ref "U49") (pin "3") (pinfunction "3_3") (pintype "unspecified"))
      (node (ref "U50") (pin "3") (pinfunction "3_3") (pintype "unspecified"))
      (node (ref "U51") (pin "3") (pinfunction "3_3") (pintype "unspecified"))
      (node (ref "U52") (pin "3") (pinfunction "3_3") (pintype "unspecified"))
      (node (ref "U53") (pin "3") (pinfunction "3_3") (pintype "unspecified"))
    )
    (net (code "27") (name "IMU_ADR") (class "Default")
      (node (ref "P4") (pin "5") (pinfunction "5_5") (pintype "unspecified"))
      (node (ref "U1") (pin "35") (pinfunction "PB14_35") (pintype "unspecified"))
    )
    (net (code "28") (name "IMU_BOOT") (class "Default")
      (node (ref "P4") (pin "7") (pinfunction "7_7") (pintype "unspecified"))
      (node (ref "U1") (pin "34") (pinfunction "PB13_34") (pintype "unspecified"))
    )
    (net (code "29") (name "IMU_RESET") (class "Default")
      (node (ref "P4") (pin "8") (pinfunction "8_8") (pintype "unspecified"))
      (node (ref "U1") (pin "33") (pinfunction "PB12_33") (pintype "unspecified"))
    )
    (net (code "30") (name "LIPO+") (class "Default")
      (node (ref "C86") (pin "2") (pinfunction "2_2") (pintype "unspecified"))
      (node (ref "C89") (pin "2") (pinfunction "2_2") (pintype "unspecified"))
      (node (ref "D3") (pin "2") (pinfunction "2_2") (pintype "input"))
      (node (ref "F2") (pin "1") (pinfunction "1_1") (pintype "unspecified"))
      (node (ref "U30") (pin "8") (pinfunction "VCC_8") (pintype "input"))
      (node (ref "U35") (pin "8") (pinfunction "VCC_8") (pintype "input"))
    )
    (net (code "31") (name "M_AIN1") (class "Default")
      (node (ref "U1") (pin "43") (pinfunction "PA10_43") (pintype "unspecified"))
      (node (ref "U10") (pin "21") (pinfunction "AIN1_21") (pintype "unspecified"))
    )
    (net (code "32") (name "M_AIN2") (class "Default")
      (node (ref "U1") (pin "40") (pinfunction "PC9_40") (pintype "unspecified"))
      (node (ref "U10") (pin "22") (pinfunction "AIN2_22") (pintype "unspecified"))
    )
    (net (code "33") (name "M_AO1") (class "Default")
      (node (ref "P1") (pin "1") (pinfunction "1_1") (pintype "input"))
      (node (ref "U10") (pin "1") (pinfunction "AO1_1") (pintype "unspecified"))
      (node (ref "U10") (pin "2") (pinfunction "AO1_2") (pintype "unspecified"))
    )
    (net (code "34") (name "M_AO2") (class "Default")
      (node (ref "P1") (pin "2") (pinfunction "2_2") (pintype "input"))
      (node (ref "U10") (pin "5") (pinfunction "AO2_5") (pintype "unspecified"))
      (node (ref "U10") (pin "6") (pinfunction "AO2_6") (pintype "unspecified"))
    )
    (net (code "35") (name "M_BIN1") (class "Default")
      (node (ref "U1") (pin "57") (pinfunction "PB5_57") (pintype "unspecified"))
      (node (ref "U10") (pin "17") (pinfunction "BIN1_17") (pintype "unspecified"))
    )
    (net (code "36") (name "M_BIN2") (class "Default")
      (node (ref "U1") (pin "39") (pinfunction "PC8_39") (pintype "unspecified"))
      (node (ref "U10") (pin "16") (pinfunction "BIN2_16") (pintype "unspecified"))
    )
    (net (code "37") (name "M_BO1") (class "Default")
      (node (ref "P2") (pin "1") (pinfunction "1_1") (pintype "input"))
      (node (ref "U10") (pin "11") (pinfunction "BO1_11") (pintype "unspecified"))
      (node (ref "U10") (pin "12") (pinfunction "BO1_12") (pintype "unspecified"))
    )
    (net (code "38") (name "M_BO2") (class "Default")
      (node (ref "P2") (pin "2") (pinfunction "2_2") (pintype "input"))
      (node (ref "U10") (pin "7") (pinfunction "BO2_7") (pintype "unspecified"))
      (node (ref "U10") (pin "8") (pinfunction "BO2_8") (pintype "unspecified"))
    )
    (net (code "39") (name "M_PWMA") (class "Default")
      (node (ref "U1") (pin "61") (pinfunction "PB8_61") (pintype "unspecified"))
      (node (ref "U10") (pin "23") (pinfunction "PWMA_23") (pintype "unspecified"))
    )
    (net (code "40") (name "M_PWMB") (class "Default")
      (node (ref "U1") (pin "62") (pinfunction "PB9_62") (pintype "unspecified"))
      (node (ref "U10") (pin "15") (pinfunction "PWMB_15") (pintype "unspecified"))
    )
    (net (code "41") (name "Net-(C88-Pad1)") (class "Default")
      (node (ref "C88") (pin "1") (pinfunction "1_1") (pintype "input"))
      (node (ref "R93") (pin "2") (pinfunction "2_2") (pintype "input"))
    )
    (net (code "42") (name "Net-(C91-Pad1)") (class "Default")
      (node (ref "C91") (pin "1") (pinfunction "1_1") (pintype "input"))
      (node (ref "R96") (pin "2") (pinfunction "2_2") (pintype "input"))
    )
    (net (code "43") (name "Net-(D11-A)") (class "Default")
      (node (ref "D11") (pin "2") (pinfunction "A_2") (pintype "unspecified"))
      (node (ref "R106") (pin "2") (pinfunction "2_2") (pintype "input"))
    )
    (net (code "44") (name "Net-(D11-C)") (class "Default")
      (node (ref "CN1") (pin "1") (pinfunction "1_1") (pintype "unspecified"))
      (node (ref "D11") (pin "1") (pinfunction "C_1") (pintype "unspecified"))
      (node (ref "F2") (pin "2") (pinfunction "2_2") (pintype "unspecified"))
    )
    (net (code "45") (name "Net-(L14-Pad1)") (class "Default")
      (node (ref "L14") (pin "1") (pinfunction "1_1") (pintype "unspecified"))
      (node (ref "L22") (pin "1") (pinfunction "1_1") (pintype "unspecified"))
      (node (ref "R102") (pin "2") (pinfunction "2_2") (pintype "input"))
      (node (ref "U36") (pin "2") (pinfunction "2_2") (pintype "unspecified"))
      (node (ref "U37") (pin "1") (pinfunction "1_1") (pintype "input"))
    )
    (net (code "46") (name "Net-(LED7-A)") (class "Default")
      (node (ref "LED7") (pin "1") (pinfunction "A_1") (pintype "unspecified"))
      (node (ref "R46") (pin "1") (pinfunction "1_1") (pintype "input"))
    )
    (net (code "47") (name "Net-(LED8-A)") (class "Default")
      (node (ref "LED8") (pin "1") (pinfunction "A_1") (pintype "unspecified"))
      (node (ref "R47") (pin "1") (pinfunction "1_1") (pintype "input"))
    )
    (net (code "48") (name "Net-(LED15-A)") (class "Default")
      (node (ref "LED15") (pin "1") (pinfunction "A_1") (pintype "unspecified"))
      (node (ref "R104") (pin "1") (pinfunction "1_1") (pintype "input"))
    )
    (net (code "49") (name "Net-(LED16-A)") (class "Default")
      (node (ref "LED16") (pin "1") (pinfunction "A_1") (pintype "unspecified"))
      (node (ref "R105") (pin "1") (pinfunction "1_1") (pintype "input"))
    )
    (net (code "50") (name "Net-(LED17-A)") (class "Default")
      (node (ref "LED17") (pin "1") (pinfunction "A_1") (pintype "unspecified"))
      (node (ref "R106") (pin "1") (pinfunction "1_1") (pintype "input"))
    )
    (net (code "51") (name "Net-(LED18-A)") (class "Default")
      (node (ref "LED18") (pin "1") (pinfunction "A_1") (pintype "unspecified"))
      (node (ref "R107") (pin "1") (pinfunction "1_1") (pintype "input"))
    )
    (net (code "52") (name "Net-(R76-Pad2)") (class "Default")
      (node (ref "R76") (pin "2") (pinfunction "2_2") (pintype "input"))
      (node (ref "SW4") (pin "3") (pinfunction "3_3") (pintype "input"))
    )
    (net (code "53") (name "Net-(R77-Pad2)") (class "Default")
      (node (ref "R77") (pin "2") (pinfunction "2_2") (pintype "input"))
      (node (ref "SW2") (pin "3") (pinfunction "3_3") (pintype "input"))
    )
    (net (code "54") (name "Net-(R78-Pad2)") (class "Default")
      (node (ref "R78") (pin "2") (pinfunction "2_2") (pintype "input"))
      (node (ref "SW3") (pin "3") (pinfunction "3_3") (pintype "input"))
    )
    (net (code "55") (name "Net-(U1-VCAP_1)") (class "Default")
      (node (ref "C99") (pin "2") (pinfunction "2_2") (pintype "unspecified"))
      (node (ref "U1") (pin "30") (pinfunction "VCAP_1_30") (pintype "unspecified"))
    )
    (net (code "56") (name "Net-(U10-VCC)") (class "Default")
      (node (ref "C84") (pin "2") (pinfunction "2_2") (pintype "input"))
      (node (ref "L20") (pin "1") (pinfunction "1_1") (pintype "unspecified"))
      (node (ref "U10") (pin "20") (pinfunction "VCC_20") (pintype "unspecified"))
    )
    (net (code "57") (name "Net-(U30-COMP)") (class "Default")
      (node (ref "C87") (pin "2") (pinfunction "2_2") (pintype "input"))
      (node (ref "C88") (pin "2") (pinfunction "2_2") (pintype "input"))
      (node (ref "U30") (pin "4") (pinfunction "COMP_4") (pintype "output"))
    )
    (net (code "58") (name "Net-(U30-FB)") (class "Default")
      (node (ref "R94") (pin "1") (pinfunction "1_1") (pintype "unspecified"))
      (node (ref "R95") (pin "2") (pinfunction "2_2") (pintype "input"))
      (node (ref "U30") (pin "5") (pinfunction "FB_5") (pintype "input"))
    )
    (net (code "59") (name "Net-(U30-OUT)") (class "Default")
      (node (ref "D4") (pin "1") (pinfunction "1_1") (pintype "unspecified"))
      (node (ref "U30") (pin "1") (pinfunction "OUT_1") (pintype "input"))
      (node (ref "U33") (pin "1") (pinfunction "1_1") (pintype "unspecified"))
    )
    (net (code "60") (name "Net-(U35-COMP)") (class "Default")
      (node (ref "C90") (pin "2") (pinfunction "2_2") (pintype "input"))
      (node (ref "C91") (pin "2") (pinfunction "2_2") (pintype "input"))
      (node (ref "U35") (pin "4") (pinfunction "COMP_4") (pintype "output"))
    )
    (net (code "61") (name "Net-(U35-FB)") (class "Default")
      (node (ref "R102") (pin "1") (pinfunction "1_1") (pintype "input"))
      (node (ref "R103") (pin "2") (pinfunction "2_2") (pintype "input"))
      (node (ref "U35") (pin "5") (pinfunction "FB_5") (pintype "input"))
    )
    (net (code "62") (name "Net-(U35-OUT)") (class "Default")
      (node (ref "D5") (pin "1") (pinfunction "1_1") (pintype "unspecified"))
      (node (ref "U35") (pin "1") (pinfunction "OUT_1") (pintype "input"))
      (node (ref "U36") (pin "1") (pinfunction "1_1") (pintype "unspecified"))
    )
    (net (code "63") (name "PA0") (class "Default")
      (node (ref "P5") (pin "3") (pinfunction "3_3") (pintype "input"))
      (node (ref "R110") (pin "2") (pinfunction "2_2") (pintype "input"))
      (node (ref "U1") (pin "14") (pinfunction "PA0_14") (pintype "unspecified"))
    )
    (net (code "64") (name "PA1") (class "Default")
      (node (ref "P5") (pin "4") (pinfunction "4_4") (pintype "input"))
      (node (ref "R111") (pin "2") (pinfunction "2_2") (pintype "input"))
      (node (ref "U1") (pin "15") (pinfunction "PA1_15") (pintype "unspecified"))
    )
    (net (code "65") (name "PA4") (class "Default")
      (node (ref "P5") (pin "5") (pinfunction "5_5") (pintype "input"))
      (node (ref "R112") (pin "2") (pinfunction "2_2") (pintype "input"))
      (node (ref "U1") (pin "20") (pinfunction "PA4_20") (pintype "unspecified"))
    )
    (net (code "66") (name "PA5") (class "Default")
      (node (ref "P5") (pin "6") (pinfunction "6_6") (pintype "input"))
      (node (ref "R113") (pin "2") (pinfunction "2_2") (pintype "input"))
      (node (ref "U1") (pin "21") (pinfunction "PA5_21") (pintype "unspecified"))
    )
    (net (code "67") (name "PB0") (class "Default")
      (node (ref "P5") (pin "2") (pinfunction "2_2") (pintype "input"))
      (node (ref "R109") (pin "2") (pinfunction "2_2") (pintype "input"))
      (node (ref "U1") (pin "26") (pinfunction "PB0_26") (pintype "unspecified"))
    )
    (net (code "68") (name "PC0") (class "Default")
      (node (ref "P5") (pin "1") (pinfunction "1_1") (pintype "input"))
      (node (ref "R108") (pin "2") (pinfunction "2_2") (pintype "input"))
      (node (ref "U1") (pin "8") (pinfunction "PC0_8") (pintype "unspecified"))
    )
    (net (code "69") (name "SPI3_CS0") (class "Default")
      (node (ref "P6") (pin "3") (pinfunction "3_3") (pintype "input"))
      (node (ref "U1") (pin "36") (pinfunction "PB15_36") (pintype "unspecified"))
    )
    (net (code "70") (name "SPI3_CS1") (class "Default")
      (node (ref "P6") (pin "2") (pinfunction "2_2") (pintype "input"))
      (node (ref "U1") (pin "58") (pinfunction "PB6_58") (pintype "unspecified"))
    )
    (net (code "71") (name "SPI3_MISO") (class "Default")
      (node (ref "P6") (pin "4") (pinfunction "4_4") (pintype "input"))
      (node (ref "U1") (pin "52") (pinfunction "PC11_52") (pintype "unspecified"))
    )
    (net (code "72") (name "SPI3_MOSI") (class "Default")
      (node (ref "P6") (pin "5") (pinfunction "5_5") (pintype "input"))
      (node (ref "U1") (pin "9") (pinfunction "PC1_9") (pintype "unspecified"))
    )
    (net (code "73") (name "SPI3_SCK") (class "Default")
      (node (ref "P6") (pin "1") (pinfunction "1_1") (pintype "input"))
      (node (ref "U1") (pin "51") (pinfunction "PC10_51") (pintype "unspecified"))
    )
    (net (code "74") (name "STLINK_JTDI") (class "Default")
      (node (ref "P3") (pin "3") (pinfunction "3_3") (pintype "input"))
      (node (ref "U1") (pin "50") (pinfunction "PA15_50") (pintype "unspecified"))
    )
    (net (code "75") (name "STLINK_NJTRST") (class "Default")
      (node (ref "P3") (pin "5") (pinfunction "5_5") (pintype "input"))
      (node (ref "U1") (pin "56") (pinfunction "PB4_56") (pintype "unspecified"))
    )
    (net (code "76") (name "STLINK_NRST") (class "Default")
      (node (ref "C66") (pin "2") (pinfunction "2_2") (pintype "input"))
      (node (ref "H1") (pin "4") (pinfunction "4_4") (pintype "input"))
      (node (ref "R52") (pin "1") (pinfunction "1_1") (pintype "input"))
      (node (ref "R76") (pin "1") (pinfunction "1_1") (pintype "input"))
      (node (ref "U1") (pin "7") (pinfunction "NRST_7") (pintype "unspecified"))
      (node (ref "U47") (pin "2") (pinfunction "2_2") (pintype "unspecified"))
    )
    (net (code "77") (name "STLINK_RX") (class "Default")
      (node (ref "H1") (pin "3") (pinfunction "3_3") (pintype "input"))
      (node (ref "U1") (pin "17") (pinfunction "PA3_17") (pintype "unspecified"))
    )
    (net (code "78") (name "STLINK_SWO") (class "Default")
      (node (ref "P3") (pin "4") (pinfunction "4_4") (pintype "input"))
      (node (ref "U1") (pin "55") (pinfunction "PB3_55") (pintype "unspecified"))
    )
    (net (code "79") (name "STLINK_TCK") (class "Default")
      (node (ref "P3") (pin "2") (pinfunction "2_2") (pintype "input"))
      (node (ref "U1") (pin "49") (pinfunction "PA14_49") (pintype "unspecified"))
    )
    (net (code "80") (name "STLINK_TMS") (class "Default")
      (node (ref "P3") (pin "1") (pinfunction "1_1") (pintype "input"))
      (node (ref "U1") (pin "46") (pinfunction "PA13_46") (pintype "unspecified"))
    )
    (net (code "81") (name "STLINK_TX") (class "Default")
      (node (ref "H1") (pin "2") (pinfunction "2_2") (pintype "input"))
      (node (ref "U1") (pin "16") (pinfunction "PA2_16") (pintype "unspecified"))
    )
    (net (code "82") (name "ST_LED1") (class "Default")
      (node (ref "R46") (pin "2") (pinfunction "2_2") (pintype "input"))
      (node (ref "U1") (pin "44") (pinfunction "PA11_44") (pintype "unspecified"))
    )
    (net (code "83") (name "ST_LED2") (class "Default")
      (node (ref "R47") (pin "2") (pinfunction "2_2") (pintype "input"))
      (node (ref "U1") (pin "45") (pinfunction "PA12_45") (pintype "unspecified"))
    )
    (net (code "84") (name "ST_LED3") (class "Default")
      (node (ref "R107") (pin "2") (pinfunction "2_2") (pintype "input"))
      (node (ref "U1") (pin "54") (pinfunction "PD2_54") (pintype "unspecified"))
    )
    (net (code "85") (name "UART_RX") (class "Default")
      (node (ref "U1") (pin "38") (pinfunction "PC7_38") (pintype "unspecified"))
      (node (ref "U47") (pin "4") (pinfunction "4_4") (pintype "unspecified"))
    )
    (net (code "86") (name "UART_TX") (class "Default")
      (node (ref "U1") (pin "37") (pinfunction "PC6_37") (pintype "unspecified"))
      (node (ref "U47") (pin "3") (pinfunction "3_3") (pintype "unspecified"))
    )
    (net (code "87") (name "unconnected-(P4-Pad6)") (class "Default")
      (node (ref "P4") (pin "6") (pinfunction "6_6") (pintype "unspecified+no_connect"))
    )
    (net (code "88") (name "unconnected-(SW2-Pad1)") (class "Default")
      (node (ref "SW2") (pin "1") (pinfunction "1_1") (pintype "input+no_connect"))
    )
    (net (code "89") (name "unconnected-(SW2-Pad4)") (class "Default")
      (node (ref "SW2") (pin "4") (pinfunction "4_4") (pintype "input+no_connect"))
    )
    (net (code "90") (name "unconnected-(SW3-Pad1)") (class "Default")
      (node (ref "SW3") (pin "1") (pinfunction "1_1") (pintype "input+no_connect"))
    )
    (net (code "91") (name "unconnected-(SW3-Pad4)") (class "Default")
      (node (ref "SW3") (pin "4") (pinfunction "4_4") (pintype "input+no_connect"))
    )
    (net (code "92") (name "unconnected-(SW4-Pad1)") (class "Default")
      (node (ref "SW4") (pin "1") (pinfunction "1_1") (pintype "input+no_connect"))
    )
    (net (code "93") (name "unconnected-(SW4-Pad4)") (class "Default")
      (node (ref "SW4") (pin "4") (pinfunction "4_4") (pintype "input+no_connect"))
    )
    (net (code "94") (name "unconnected-(U1-PC14-OSC32_IN-Pad3)") (class "Default")
      (node (ref "U1") (pin "3") (pinfunction "PC14-OSC32_IN_3") (pintype "unspecified+no_connect"))
    )
    (net (code "95") (name "unconnected-(U1-PC15-OSC32_OUT-Pad4)") (class "Default")
      (node (ref "U1") (pin "4") (pinfunction "PC15-OSC32_OUT_4") (pintype "unspecified+no_connect"))
    )
    (net (code "96") (name "unconnected-(U1-PH0-OSC_IN-Pad5)") (class "Default")
      (node (ref "U1") (pin "5") (pinfunction "PH0-OSC_IN_5") (pintype "unspecified+no_connect"))
    )
    (net (code "97") (name "unconnected-(U1-PH1-OSC_OUT-Pad6)") (class "Default")
      (node (ref "U1") (pin "6") (pinfunction "PH1-OSC_OUT_6") (pintype "unspecified+no_connect"))
    )
    (net (code "98") (name "unconnected-(U30-SYNC-Pad2)") (class "Default")
      (node (ref "U30") (pin "2") (pinfunction "SYNC_2") (pintype "input+no_connect"))
    )
    (net (code "99") (name "unconnected-(U30-VREF-Pad6)") (class "Default")
      (node (ref "U30") (pin "6") (pinfunction "VREF_6") (pintype "input+no_connect"))
    )
    (net (code "100") (name "unconnected-(U35-SYNC-Pad2)") (class "Default")
      (node (ref "U35") (pin "2") (pinfunction "SYNC_2") (pintype "input+no_connect"))
    )
    (net (code "101") (name "unconnected-(U35-VREF-Pad6)") (class "Default")
      (node (ref "U35") (pin "6") (pinfunction "VREF_6") (pintype "input+no_connect"))
    )
  )
)
